# EDCPSUMK1-RP2040-USBC.net
KiCad netlist of a schematic drawn in EAGLE
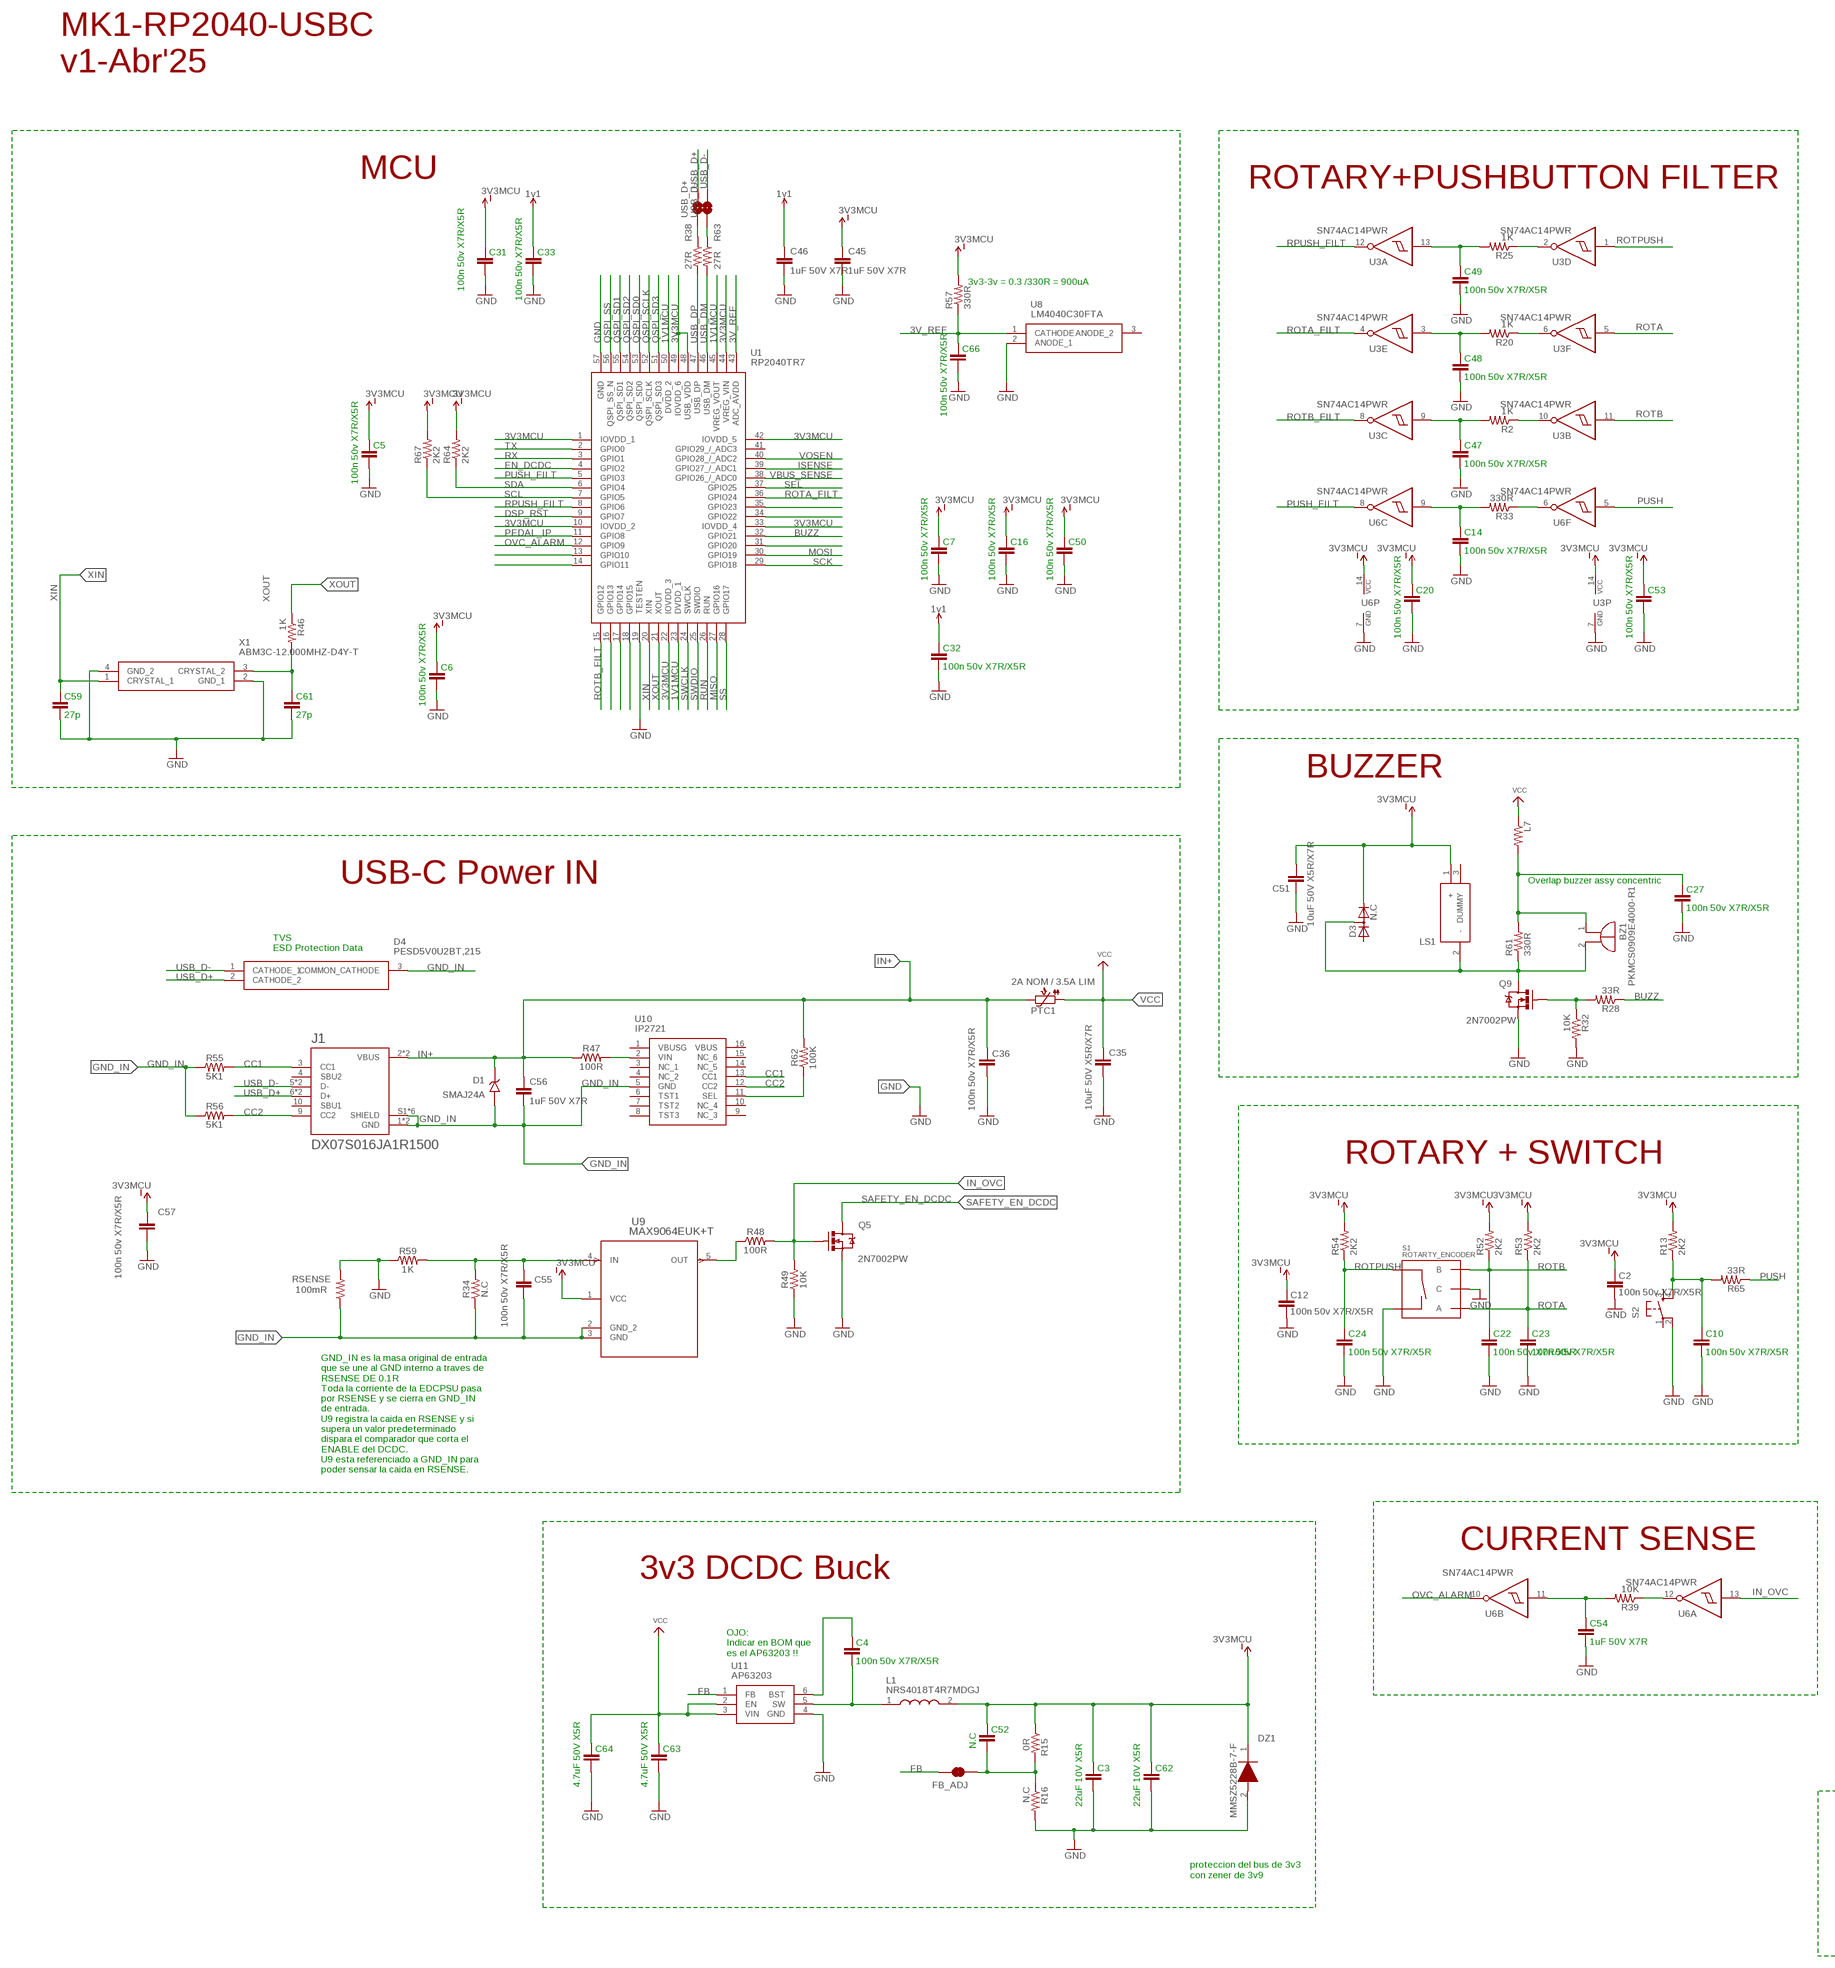
[diagram p0: schematic, sheet 1, part 1 of 2]
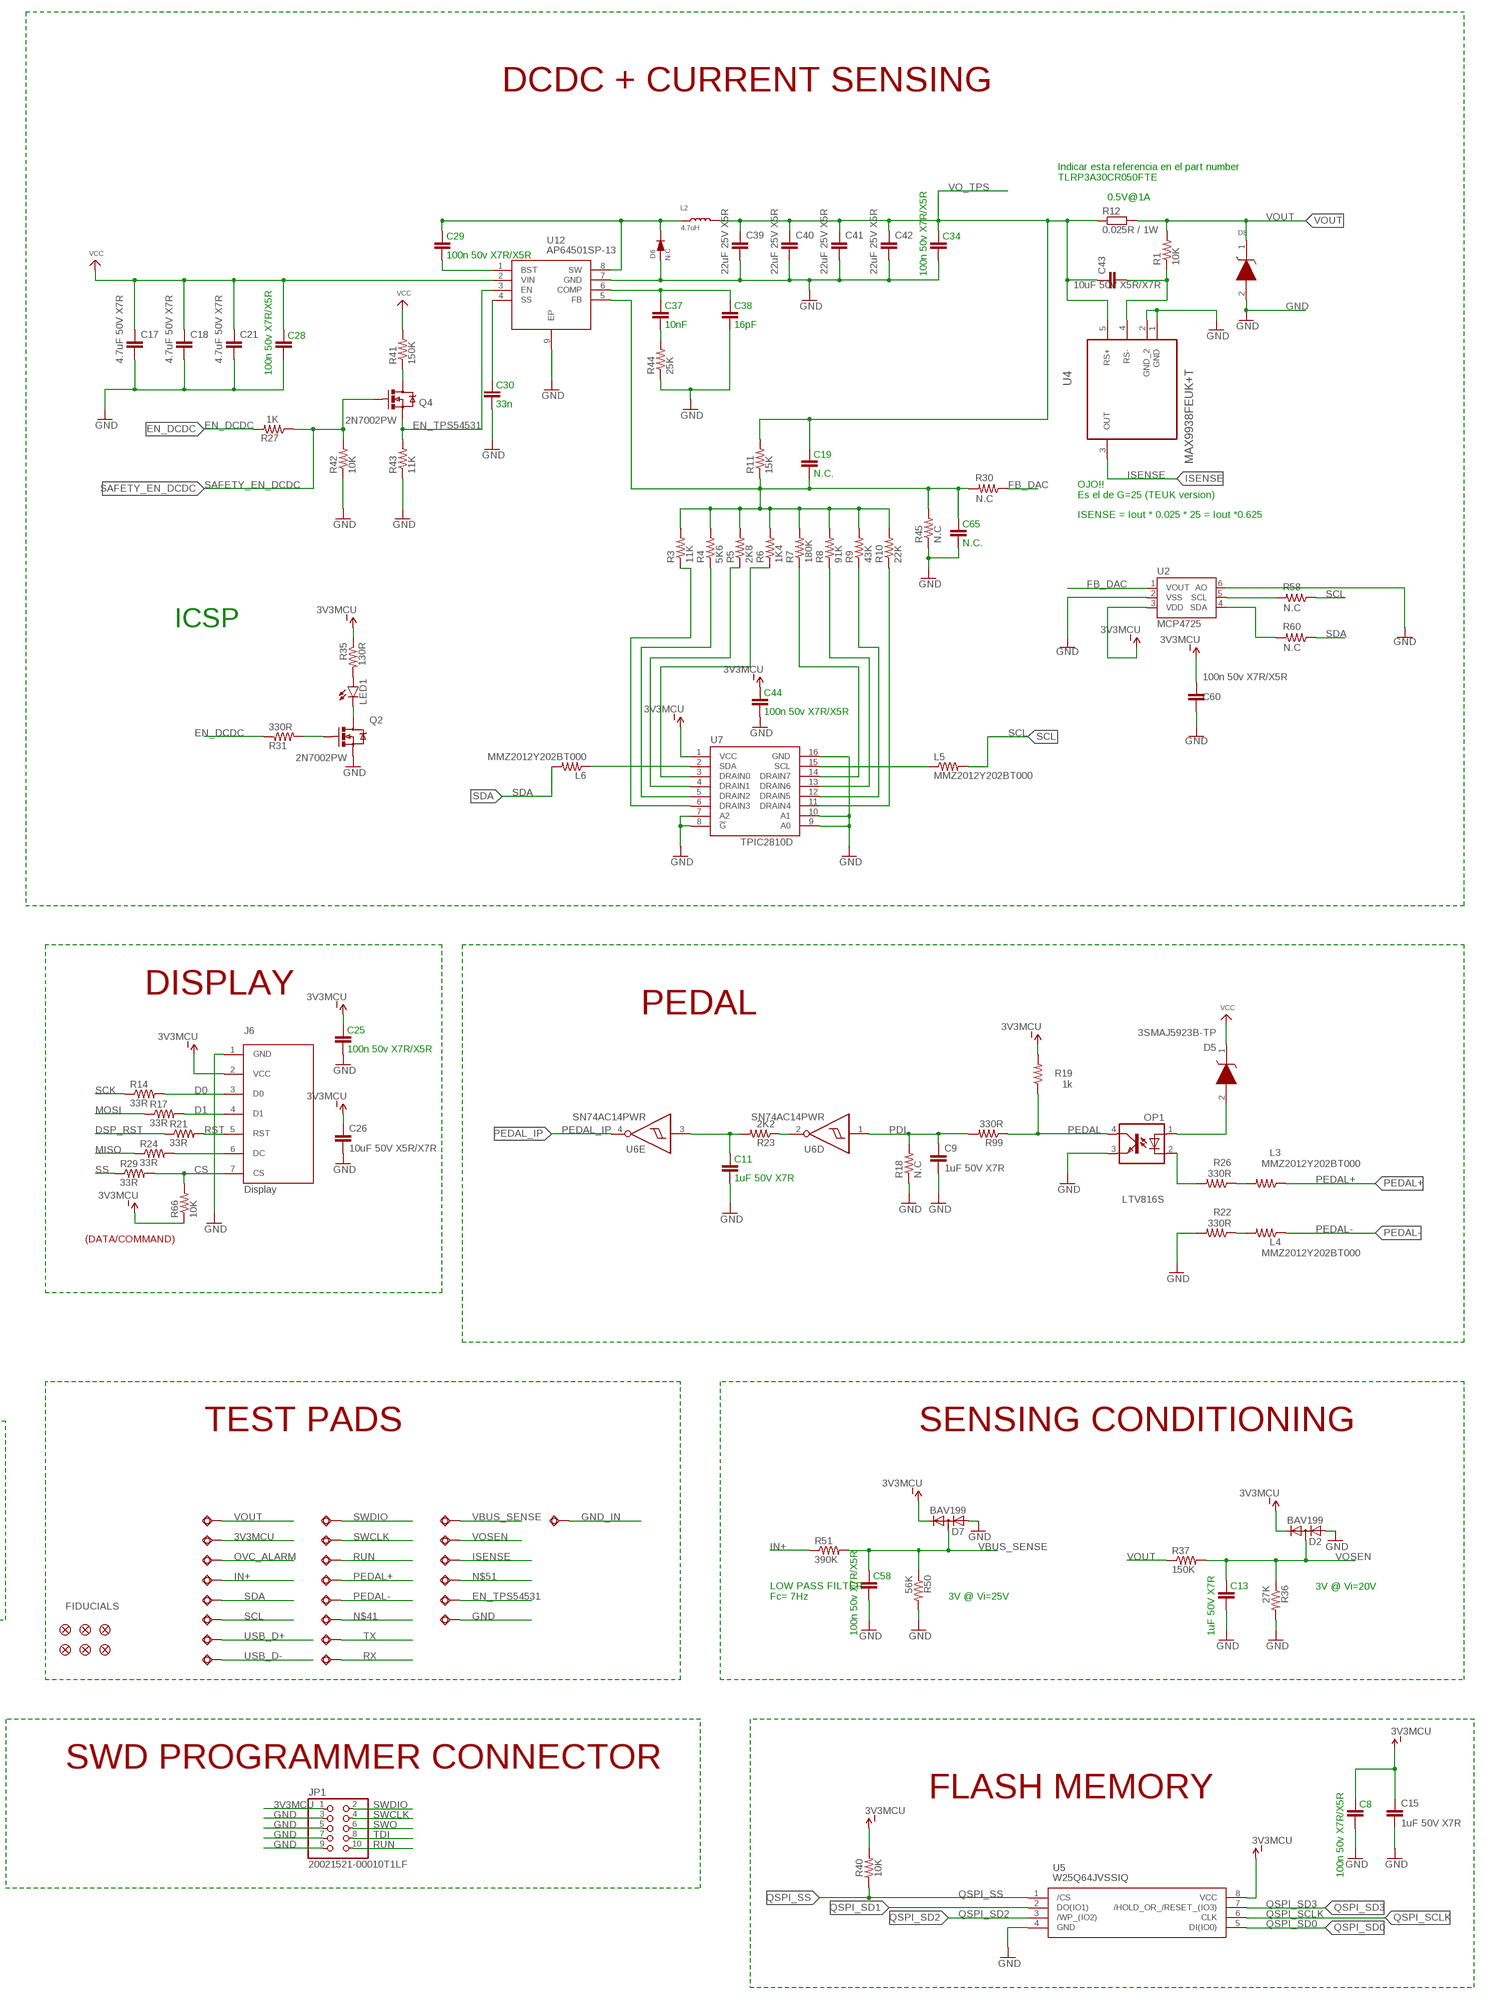
[diagram p1: schematic, sheet 1, part 2 of 2]

(export (version "E")
  (design (tool "Eeschema 10.0.6"))
  (components
    (comp (ref "3V3MCU")
      (value "TESTPAD_TPSQB1,27")
      (footprint "eagle-import:TESTPAD_B1,27")
      (libsource (lib "eagle-import") (part "TESTPAD_TPSQB1,27"))
    )
    (comp (ref "BZ1")
      (value "PKMCS0909E4000-R1")
      (footprint "eagle-import:PKMCS0909")
      (libsource (lib "eagle-import") (part "PKMCS0909E4000-R1"))
    )
    (comp (ref "C2")
      (value "100n 50v X7R/X5R")
      (footprint "eagle-import:0805")
      (libsource (lib "eagle-import") (part "CAP0805"))
    )
    (comp (ref "C3")
      (value "22uF 10V X5R")
      (footprint "eagle-import:0805")
      (libsource (lib "eagle-import") (part "CAP0805"))
    )
    (comp (ref "C4")
      (value "100n 50v X7R/X5R")
      (footprint "eagle-import:0805")
      (libsource (lib "eagle-import") (part "CAP0805"))
    )
    (comp (ref "C5")
      (value "100n 50v X7R/X5R")
      (footprint "eagle-import:0805")
      (libsource (lib "eagle-import") (part "CAP0805"))
    )
    (comp (ref "C6")
      (value "100n 50v X7R/X5R")
      (footprint "eagle-import:0805")
      (libsource (lib "eagle-import") (part "CAP0805"))
    )
    (comp (ref "C7")
      (value "100n 50v X7R/X5R")
      (footprint "eagle-import:0805")
      (libsource (lib "eagle-import") (part "CAP0805"))
    )
    (comp (ref "C8")
      (value "100n 50v X7R/X5R")
      (footprint "eagle-import:0805")
      (libsource (lib "eagle-import") (part "CAP0805"))
    )
    (comp (ref "C9")
      (value "1uF 50V X7R")
      (footprint "eagle-import:0805")
      (libsource (lib "eagle-import") (part "CAP0805"))
    )
    (comp (ref "C10")
      (value "100n 50v X7R/X5R")
      (footprint "eagle-import:0805")
      (libsource (lib "eagle-import") (part "CAP0805"))
    )
    (comp (ref "C11")
      (value "1uF 50V X7R")
      (footprint "eagle-import:0805")
      (libsource (lib "eagle-import") (part "CAP0805"))
    )
    (comp (ref "C12")
      (value "100n 50v X7R/X5R")
      (footprint "eagle-import:0805")
      (libsource (lib "eagle-import") (part "CAP0805"))
    )
    (comp (ref "C13")
      (value "1uF 50V X7R")
      (footprint "eagle-import:0805")
      (libsource (lib "eagle-import") (part "CAP0805"))
    )
    (comp (ref "C14")
      (value "100n 50v X7R/X5R")
      (footprint "eagle-import:0805")
      (libsource (lib "eagle-import") (part "CAP0805"))
    )
    (comp (ref "C15")
      (value "1uF 50V X7R")
      (footprint "eagle-import:0805")
      (libsource (lib "eagle-import") (part "CAP0805"))
    )
    (comp (ref "C16")
      (value "100n 50v X7R/X5R")
      (footprint "eagle-import:0805")
      (libsource (lib "eagle-import") (part "CAP0805"))
    )
    (comp (ref "C17")
      (value "4.7uF 50V X7R")
      (footprint "eagle-import:1210")
      (libsource (lib "eagle-import") (part "CAP1210"))
    )
    (comp (ref "C18")
      (value "4.7uF 50V X7R")
      (footprint "eagle-import:1210")
      (libsource (lib "eagle-import") (part "CAP1210"))
    )
    (comp (ref "C19")
      (value "N.C.")
      (footprint "eagle-import:0805")
      (libsource (lib "eagle-import") (part "CAP0805"))
    )
    (comp (ref "C20")
      (value "100n 50v X7R/X5R")
      (footprint "eagle-import:0805")
      (libsource (lib "eagle-import") (part "CAP0805"))
    )
    (comp (ref "C21")
      (value "4.7uF 50V X7R")
      (footprint "eagle-import:1210")
      (libsource (lib "eagle-import") (part "CAP1210"))
    )
    (comp (ref "C22")
      (value "100n 50v X7R/X5R")
      (footprint "eagle-import:0805")
      (libsource (lib "eagle-import") (part "CAP0805"))
    )
    (comp (ref "C23")
      (value "100n 50v X7R/X5R")
      (footprint "eagle-import:0805")
      (libsource (lib "eagle-import") (part "CAP0805"))
    )
    (comp (ref "C24")
      (value "100n 50v X7R/X5R")
      (footprint "eagle-import:0805")
      (libsource (lib "eagle-import") (part "CAP0805"))
    )
    (comp (ref "C25")
      (value "100n 50v X7R/X5R")
      (footprint "eagle-import:0805")
      (libsource (lib "eagle-import") (part "CAP0805"))
    )
    (comp (ref "C26")
      (value "10uF 50V X5R/X7R")
      (footprint "eagle-import:1206")
      (libsource (lib "eagle-import") (part "CAP1206"))
    )
    (comp (ref "C27")
      (value "100n 50v X7R/X5R")
      (footprint "eagle-import:0805")
      (libsource (lib "eagle-import") (part "CAP0805"))
    )
    (comp (ref "C28")
      (value "100n 50v X7R/X5R")
      (footprint "eagle-import:0805")
      (libsource (lib "eagle-import") (part "CAP0805"))
    )
    (comp (ref "C29")
      (value "100n 50v X7R/X5R")
      (footprint "eagle-import:0805")
      (libsource (lib "eagle-import") (part "CAP0805"))
    )
    (comp (ref "C30")
      (value "33n")
      (footprint "eagle-import:0805")
      (libsource (lib "eagle-import") (part "CAP0805"))
    )
    (comp (ref "C31")
      (value "100n 50v X7R/X5R")
      (footprint "eagle-import:0805")
      (libsource (lib "eagle-import") (part "CAP0805"))
    )
    (comp (ref "C32")
      (value "100n 50v X7R/X5R")
      (footprint "eagle-import:0805")
      (libsource (lib "eagle-import") (part "CAP0805"))
    )
    (comp (ref "C33")
      (value "100n 50v X7R/X5R")
      (footprint "eagle-import:0805")
      (libsource (lib "eagle-import") (part "CAP0805"))
    )
    (comp (ref "C34")
      (value "100n 50v X7R/X5R")
      (footprint "eagle-import:0805")
      (libsource (lib "eagle-import") (part "CAP0805"))
    )
    (comp (ref "C35")
      (value "10uF 50V X5R/X7R")
      (footprint "eagle-import:1206")
      (libsource (lib "eagle-import") (part "CAP1206"))
    )
    (comp (ref "C36")
      (value "100n 50v X7R/X5R")
      (footprint "eagle-import:0805")
      (libsource (lib "eagle-import") (part "CAP0805"))
    )
    (comp (ref "C37")
      (value "10nF")
      (footprint "eagle-import:0805")
      (libsource (lib "eagle-import") (part "CAP0805"))
    )
    (comp (ref "C38")
      (value "16pF")
      (footprint "eagle-import:0805")
      (libsource (lib "eagle-import") (part "CAP0805"))
    )
    (comp (ref "C39")
      (value "22uF 25V X5R")
      (footprint "eagle-import:1210")
      (libsource (lib "eagle-import") (part "CAP1210"))
    )
    (comp (ref "C40")
      (value "22uF 25V X5R")
      (footprint "eagle-import:1210")
      (libsource (lib "eagle-import") (part "CAP1210"))
    )
    (comp (ref "C41")
      (value "22uF 25V X5R")
      (footprint "eagle-import:1210")
      (libsource (lib "eagle-import") (part "CAP1210"))
    )
    (comp (ref "C42")
      (value "22uF 25V X5R")
      (footprint "eagle-import:1210")
      (libsource (lib "eagle-import") (part "CAP1210"))
    )
    (comp (ref "C43")
      (value "10uF 50V X5R/X7R")
      (footprint "eagle-import:1206")
      (libsource (lib "eagle-import") (part "CAP1206"))
    )
    (comp (ref "C44")
      (value "100n 50v X7R/X5R")
      (footprint "eagle-import:0805")
      (libsource (lib "eagle-import") (part "CAP0805"))
    )
    (comp (ref "C45")
      (value "1uF 50V X7R")
      (footprint "eagle-import:0805")
      (libsource (lib "eagle-import") (part "CAP0805"))
    )
    (comp (ref "C46")
      (value "1uF 50V X7R")
      (footprint "eagle-import:0805")
      (libsource (lib "eagle-import") (part "CAP0805"))
    )
    (comp (ref "C47")
      (value "100n 50v X7R/X5R")
      (footprint "eagle-import:0805")
      (libsource (lib "eagle-import") (part "CAP0805"))
    )
    (comp (ref "C48")
      (value "100n 50v X7R/X5R")
      (footprint "eagle-import:0805")
      (libsource (lib "eagle-import") (part "CAP0805"))
    )
    (comp (ref "C49")
      (value "100n 50v X7R/X5R")
      (footprint "eagle-import:0805")
      (libsource (lib "eagle-import") (part "CAP0805"))
    )
    (comp (ref "C50")
      (value "100n 50v X7R/X5R")
      (footprint "eagle-import:0805")
      (libsource (lib "eagle-import") (part "CAP0805"))
    )
    (comp (ref "C51")
      (value "10uF 50V X5R/X7R")
      (footprint "eagle-import:1206")
      (libsource (lib "eagle-import") (part "CAP1206"))
    )
    (comp (ref "C52")
      (value "N.C")
      (footprint "eagle-import:0805")
      (libsource (lib "eagle-import") (part "CAP0805"))
    )
    (comp (ref "C53")
      (value "100n 50v X7R/X5R")
      (footprint "eagle-import:0805")
      (libsource (lib "eagle-import") (part "CAP0805"))
    )
    (comp (ref "C54")
      (value "1uF 50V X7R")
      (footprint "eagle-import:0805")
      (libsource (lib "eagle-import") (part "CAP0805"))
    )
    (comp (ref "C55")
      (value "100n 50v X7R/X5R")
      (footprint "eagle-import:0805")
      (libsource (lib "eagle-import") (part "CAP0805"))
    )
    (comp (ref "C56")
      (value "1uF 50V X7R")
      (footprint "eagle-import:0805")
      (libsource (lib "eagle-import") (part "CAP0805"))
    )
    (comp (ref "C57")
      (value "100n 50v X7R/X5R")
      (footprint "eagle-import:0805")
      (libsource (lib "eagle-import") (part "CAP0805"))
    )
    (comp (ref "C58")
      (value "100n 50v X7R/X5R")
      (footprint "eagle-import:0805")
      (libsource (lib "eagle-import") (part "CAP0805"))
    )
    (comp (ref "C59")
      (value "27p")
      (footprint "eagle-import:0805")
      (libsource (lib "eagle-import") (part "CAP0805"))
    )
    (comp (ref "C60")
      (value "100n 50v X7R/X5R")
      (footprint "eagle-import:0805")
      (libsource (lib "eagle-import") (part "CAP0805"))
    )
    (comp (ref "C61")
      (value "27p")
      (footprint "eagle-import:0805")
      (libsource (lib "eagle-import") (part "CAP0805"))
    )
    (comp (ref "C62")
      (value "22uF 10V X5R")
      (footprint "eagle-import:0805")
      (libsource (lib "eagle-import") (part "CAP0805"))
    )
    (comp (ref "C63")
      (value "4.7uF 50V X5R")
      (footprint "eagle-import:0805")
      (libsource (lib "eagle-import") (part "CAP0805"))
    )
    (comp (ref "C64")
      (value "4.7uF 50V X5R")
      (footprint "eagle-import:0805")
      (libsource (lib "eagle-import") (part "CAP0805"))
    )
    (comp (ref "C65")
      (value "N.C.")
      (footprint "eagle-import:0805")
      (libsource (lib "eagle-import") (part "CAP0805"))
    )
    (comp (ref "C66")
      (value "100n 50v X7R/X5R")
      (footprint "eagle-import:0805")
      (libsource (lib "eagle-import") (part "CAP0805"))
    )
    (comp (ref "D1")
      (value "SMAJ24A")
      (footprint "eagle-import:DIOM4325X244N")
      (fields (field (name "MF") "Micro Commercial Components") (field (name "MP") "3SMAJ5934B"))
      (libsource (lib "eagle-import") (part "3SMAJ5934B"))
    )
    (comp (ref "D2")
      (value "BAV199")
      (footprint "eagle-import:SOT23")
      (libsource (lib "eagle-import") (part "BAV199"))
    )
    (comp (ref "D3")
      (value "N.C")
      (footprint "eagle-import:SOT23")
      (libsource (lib "eagle-import") (part "BAV199"))
    )
    (comp (ref "D4")
      (value "PESD5V0U2BT,215")
      (footprint "eagle-import:SOT95P230X110-3N")
      (fields (field (name "MOUSER_PART_NUMBER") "771-PESD5V0U2BTT/R"))
      (libsource (lib "eagle-import") (part "PESD5V0U2BT,215"))
    )
    (comp (ref "D5")
      (value "3SMAJ5923B-TP")
      (footprint "eagle-import:DIOM5226X244N")
      (fields (field (name "MOUSER_PART_NUMBER") "833-3SMAJ5923B-TP"))
      (libsource (lib "eagle-import") (part "3SMAJ5923B-TP"))
    )
    (comp (ref "D6")
      (value "N.C")
      (footprint "eagle-import:DO-214AB")
      (libsource (lib "eagle-import") (part "DSMC"))
    )
    (comp (ref "D7")
      (value "BAV199")
      (footprint "eagle-import:SOT23")
      (libsource (lib "eagle-import") (part "BAV199"))
    )
    (comp (ref "D8")
      (value "RB060M-60TR")
      (footprint "eagle-import:DIOM5226X244N")
      (fields
        (field (name "ARROW_PART_NUMBER") "3SMAJ5923B-TP")
        (field (name "MOUSER_PART_NUMBER") "833-3SMAJ5923B-TP")
      )
      (libsource (lib "eagle-import") (part "3SMAJ5923B-TP"))
    )
    (comp (ref "DZ1")
      (value "MMSZ5228B-7-F")
      (footprint "eagle-import:SODFL3518X115N")
      (libsource (lib "eagle-import") (part "MMSZ5228B-7-F"))
    )
    (comp (ref "EN_TPS54531")
      (value "TESTPAD_TPSQB1,27")
      (footprint "eagle-import:TESTPAD_B1,27")
      (libsource (lib "eagle-import") (part "TESTPAD_TPSQB1,27"))
    )
    (comp (ref "FB_ADJ")
      (value "JUMPER-SMT_2_NC_TRACE_NO-SILK")
      (footprint "eagle-import:SMT-JUMPER_2_NC_TRACE_NO-SILK")
      (libsource (lib "eagle-import") (part "JUMPER-SMT_2_NC_TRACE_NO-SILK"))
    )
    (comp (ref "FID1")
      (value "FIDUCIAL1X2")
      (footprint "eagle-import:FIDUCIAL-1X2")
      (libsource (lib "eagle-import") (part "FIDUCIAL1X2"))
    )
    (comp (ref "FID2")
      (value "FIDUCIAL1X2")
      (footprint "eagle-import:FIDUCIAL-1X2")
      (libsource (lib "eagle-import") (part "FIDUCIAL1X2"))
    )
    (comp (ref "FID3")
      (value "FIDUCIAL1X2")
      (footprint "eagle-import:FIDUCIAL-1X2")
      (libsource (lib "eagle-import") (part "FIDUCIAL1X2"))
    )
    (comp (ref "FID4")
      (value "FIDUCIAL1X2")
      (footprint "eagle-import:FIDUCIAL-1X2")
      (libsource (lib "eagle-import") (part "FIDUCIAL1X2"))
    )
    (comp (ref "FID5")
      (value "FIDUCIAL1X2")
      (footprint "eagle-import:FIDUCIAL-1X2")
      (libsource (lib "eagle-import") (part "FIDUCIAL1X2"))
    )
    (comp (ref "FID6")
      (value "FIDUCIAL1X2")
      (footprint "eagle-import:FIDUCIAL-1X2")
      (libsource (lib "eagle-import") (part "FIDUCIAL1X2"))
    )
    (comp (ref "GND")
      (value "TESTPAD_TPSQB1,27")
      (footprint "eagle-import:TESTPAD_B1,27")
      (libsource (lib "eagle-import") (part "TESTPAD_TPSQB1,27"))
    )
    (comp (ref "GND_IN")
      (value "TESTPAD_TPSQB1,27")
      (footprint "eagle-import:TESTPAD_B1,27")
      (libsource (lib "eagle-import") (part "TESTPAD_TPSQB1,27"))
    )
    (comp (ref "IN+")
      (value "TESTPAD_TPSQB1,27")
      (footprint "eagle-import:TESTPAD_B1,27")
      (libsource (lib "eagle-import") (part "TESTPAD_TPSQB1,27"))
    )
    (comp (ref "ISENSE")
      (value "TESTPAD_TPSQB1,27")
      (footprint "eagle-import:TESTPAD_B1,27")
      (libsource (lib "eagle-import") (part "TESTPAD_TPSQB1,27"))
    )
    (comp (ref "J1")
      (value "DX07S016JA1R1500")
      (footprint "eagle-import:JAE_DX07S016JA1R1500")
      (fields
        (field (name "DIGI-KEY_PART_NUMBER") "670-DX07S016JA1R1500CT-ND")
        (field (name "MF") "JAE Electronics")
      )
      (libsource (lib "eagle-import") (part "DX07S016JA1R1500"))
    )
    (comp (ref "J6")
      (value "Display")
      (footprint "eagle-import:OLED_LCD")
      (libsource (lib "eagle-import") (part "OLED_LCD"))
    )
    (comp (ref "JP1")
      (value "20021521-00010T1LF")
      (footprint "eagle-import:20021521-00010T1LF")
      (fields (field (name "DIGI-KEY_PART_NUMBER") "609-4054-ND") (field (name "MF") "AMPHENOL ICC / FCI"))
      (libsource (lib "eagle-import") (part "20021521-00010T1LF"))
    )
    (comp (ref "L1")
      (value "NRS4018T4R7MDGJ")
      (footprint "eagle-import:NRS4018T100MDGJ")
      (fields (field (name "MOUSER_PART_NUMBER") "963-NRS4018T4R7MDGJ"))
      (libsource (lib "eagle-import") (part "NRS4018T4R7MDGJ"))
    )
    (comp (ref "L2")
      (value "4.7uH")
      (footprint "eagle-import:WE-LHMI")
      (libsource (lib "eagle-import") (part "L74437368047"))
    )
    (comp (ref "L3")
      (value "MMZ2012Y202BT000")
      (footprint "eagle-import:0805")
      (libsource (lib "eagle-import") (part "RESISTOR0805-RES"))
    )
    (comp (ref "L4")
      (value "MMZ2012Y202BT000")
      (footprint "eagle-import:0805")
      (libsource (lib "eagle-import") (part "RESISTOR0805-RES"))
    )
    (comp (ref "L5")
      (value "MMZ2012Y202BT000")
      (footprint "eagle-import:0805")
      (libsource (lib "eagle-import") (part "RESISTOR0805-RES"))
    )
    (comp (ref "L6")
      (value "MMZ2012Y202BT000")
      (footprint "eagle-import:0805")
      (libsource (lib "eagle-import") (part "RESISTOR0805-RES"))
    )
    (comp (ref "L7")
      (value "MMZ2012Y202BT000")
      (footprint "eagle-import:0805")
      (libsource (lib "eagle-import") (part "RESISTOR0805-RES"))
    )
    (comp (ref "LED1")
      (value "LED3MM")
      (footprint "eagle-import:LED3MM")
      (libsource (lib "eagle-import") (part "LED3MM"))
    )
    (comp (ref "LS1")
      (value "SMT-0540-S-R")
      (footprint "eagle-import:SMT0540SR")
      (fields (field (name "MOUSER_PART_NUMBER") "665-SMT0540SR"))
      (libsource (lib "eagle-import") (part "SMT-0540-S-R"))
    )
    (comp (ref "N$41")
      (value "TESTPAD_TPSQB1,27")
      (footprint "eagle-import:TESTPAD_B1,27")
      (libsource (lib "eagle-import") (part "TESTPAD_TPSQB1,27"))
    )
    (comp (ref "N$51")
      (value "TESTPAD_TPSQB1,27")
      (footprint "eagle-import:TESTPAD_B1,27")
      (libsource (lib "eagle-import") (part "TESTPAD_TPSQB1,27"))
    )
    (comp (ref "OP1")
      (value "LTV816S")
      (footprint "eagle-import:SMD4")
      (libsource (lib "eagle-import") (part "LTV816S"))
    )
    (comp (ref "OVC_ALARM")
      (value "TESTPAD_TPSQB1,27")
      (footprint "eagle-import:TESTPAD_B1,27")
      (libsource (lib "eagle-import") (part "TESTPAD_TPSQB1,27"))
    )
    (comp (ref "PEDAL+")
      (value "TESTPAD_TPSQB1,27")
      (footprint "eagle-import:TESTPAD_B1,27")
      (libsource (lib "eagle-import") (part "TESTPAD_TPSQB1,27"))
    )
    (comp (ref "PEDAL-")
      (value "TESTPAD_TPSQB1,27")
      (footprint "eagle-import:TESTPAD_B1,27")
      (libsource (lib "eagle-import") (part "TESTPAD_TPSQB1,27"))
    )
    (comp (ref "PTC1")
      (value "2A NOM / 3.5A LIM")
      (footprint "eagle-import:1812L")
      (libsource (lib "eagle-import") (part "PTC-"))
    )
    (comp (ref "Q2")
      (value "2N7002PW")
      (footprint "eagle-import:SOT323")
      (libsource (lib "eagle-import") (part "MOSFET-NCHANNEL2N7002PW"))
    )
    (comp (ref "Q4")
      (value "2N7002PW")
      (footprint "eagle-import:SOT323")
      (libsource (lib "eagle-import") (part "MOSFET-NCHANNEL2N7002PW"))
    )
    (comp (ref "Q5")
      (value "2N7002PW")
      (footprint "eagle-import:SOT323")
      (libsource (lib "eagle-import") (part "MOSFET-NCHANNEL2N7002PW"))
    )
    (comp (ref "Q9")
      (value "2N7002PW")
      (footprint "eagle-import:SOT323")
      (libsource (lib "eagle-import") (part "MOSFET-NCHANNEL2N7002PW"))
    )
    (comp (ref "R1")
      (value "10K")
      (footprint "eagle-import:0805")
      (libsource (lib "eagle-import") (part "RESISTOR0805"))
    )
    (comp (ref "R2")
      (value "1K")
      (footprint "eagle-import:0805")
      (libsource (lib "eagle-import") (part "RESISTOR0805"))
    )
    (comp (ref "R3")
      (value "11K")
      (footprint "eagle-import:0805")
      (libsource (lib "eagle-import") (part "RESISTOR0805"))
    )
    (comp (ref "R4")
      (value "5K6")
      (footprint "eagle-import:0805")
      (libsource (lib "eagle-import") (part "RESISTOR0805"))
    )
    (comp (ref "R5")
      (value "2K8")
      (footprint "eagle-import:0805")
      (libsource (lib "eagle-import") (part "RESISTOR0805"))
    )
    (comp (ref "R6")
      (value "1K4")
      (footprint "eagle-import:0805")
      (libsource (lib "eagle-import") (part "RESISTOR0805"))
    )
    (comp (ref "R7")
      (value "180K")
      (footprint "eagle-import:0805")
      (libsource (lib "eagle-import") (part "RESISTOR0805"))
    )
    (comp (ref "R8")
      (value "91K")
      (footprint "eagle-import:0805")
      (libsource (lib "eagle-import") (part "RESISTOR0805"))
    )
    (comp (ref "R9")
      (value "43K")
      (footprint "eagle-import:0805")
      (libsource (lib "eagle-import") (part "RESISTOR0805"))
    )
    (comp (ref "R10")
      (value "22K")
      (footprint "eagle-import:0805")
      (libsource (lib "eagle-import") (part "RESISTOR0805"))
    )
    (comp (ref "R11")
      (value "15K")
      (footprint "eagle-import:0805")
      (libsource (lib "eagle-import") (part "RESISTOR0805"))
    )
    (comp (ref "R12")
      (value "0.025R / 1W")
      (footprint "eagle-import:R2512")
      (libsource (lib "eagle-import") (part "RR2512"))
    )
    (comp (ref "R13")
      (value "2K2")
      (footprint "eagle-import:0805")
      (libsource (lib "eagle-import") (part "RESISTOR0805"))
    )
    (comp (ref "R14")
      (value "33R")
      (footprint "eagle-import:0805")
      (libsource (lib "eagle-import") (part "RESISTOR0805"))
    )
    (comp (ref "R15")
      (value "0R")
      (footprint "eagle-import:0805")
      (libsource (lib "eagle-import") (part "RESISTOR0805"))
    )
    (comp (ref "R16")
      (value "N.C")
      (footprint "eagle-import:0805")
      (libsource (lib "eagle-import") (part "RESISTOR0805"))
    )
    (comp (ref "R17")
      (value "33R")
      (footprint "eagle-import:0805")
      (libsource (lib "eagle-import") (part "RESISTOR0805"))
    )
    (comp (ref "R18")
      (value "N.C")
      (footprint "eagle-import:0805")
      (libsource (lib "eagle-import") (part "RESISTOR0805"))
    )
    (comp (ref "R19")
      (value "1k")
      (footprint "eagle-import:0805")
      (libsource (lib "eagle-import") (part "RESISTOR0805"))
    )
    (comp (ref "R20")
      (value "1K")
      (footprint "eagle-import:0805")
      (libsource (lib "eagle-import") (part "RESISTOR0805"))
    )
    (comp (ref "R21")
      (value "33R")
      (footprint "eagle-import:0805")
      (libsource (lib "eagle-import") (part "RESISTOR0805"))
    )
    (comp (ref "R22")
      (value "330R")
      (footprint "eagle-import:0805")
      (libsource (lib "eagle-import") (part "RESISTOR0805"))
    )
    (comp (ref "R23")
      (value "2K2")
      (footprint "eagle-import:0805")
      (libsource (lib "eagle-import") (part "RESISTOR0805"))
    )
    (comp (ref "R24")
      (value "33R")
      (footprint "eagle-import:0805")
      (libsource (lib "eagle-import") (part "RESISTOR0805"))
    )
    (comp (ref "R25")
      (value "1K")
      (footprint "eagle-import:0805")
      (libsource (lib "eagle-import") (part "RESISTOR0805"))
    )
    (comp (ref "R26")
      (value "330R")
      (footprint "eagle-import:0805")
      (libsource (lib "eagle-import") (part "RESISTOR0805"))
    )
    (comp (ref "R27")
      (value "1K")
      (footprint "eagle-import:0805")
      (libsource (lib "eagle-import") (part "RESISTOR0805"))
    )
    (comp (ref "R28")
      (value "33R")
      (footprint "eagle-import:0805")
      (libsource (lib "eagle-import") (part "RESISTOR0805"))
    )
    (comp (ref "R29")
      (value "33R")
      (footprint "eagle-import:0805")
      (libsource (lib "eagle-import") (part "RESISTOR0805"))
    )
    (comp (ref "R30")
      (value "N.C")
      (footprint "eagle-import:0805")
      (libsource (lib "eagle-import") (part "RESISTOR0805"))
    )
    (comp (ref "R31")
      (value "330R")
      (footprint "eagle-import:0805")
      (libsource (lib "eagle-import") (part "RESISTOR0805"))
    )
    (comp (ref "R32")
      (value "10K")
      (footprint "eagle-import:0805")
      (libsource (lib "eagle-import") (part "RESISTOR0805"))
    )
    (comp (ref "R33")
      (value "330R")
      (footprint "eagle-import:0805")
      (libsource (lib "eagle-import") (part "RESISTOR0805"))
    )
    (comp (ref "R34")
      (value "N.C")
      (footprint "eagle-import:0805")
      (libsource (lib "eagle-import") (part "RESISTOR0805"))
    )
    (comp (ref "R35")
      (value "130R")
      (footprint "eagle-import:0805")
      (libsource (lib "eagle-import") (part "RESISTOR0805"))
    )
    (comp (ref "R36")
      (value "27K")
      (footprint "eagle-import:0805")
      (libsource (lib "eagle-import") (part "RESISTOR0805"))
    )
    (comp (ref "R37")
      (value "150K")
      (footprint "eagle-import:0805")
      (libsource (lib "eagle-import") (part "RESISTOR0805"))
    )
    (comp (ref "R38")
      (value "27R")
      (footprint "eagle-import:0805")
      (libsource (lib "eagle-import") (part "RESISTOR0805"))
    )
    (comp (ref "R39")
      (value "10K")
      (footprint "eagle-import:0805")
      (libsource (lib "eagle-import") (part "RESISTOR0805"))
    )
    (comp (ref "R40")
      (value "10K")
      (footprint "eagle-import:0805")
      (libsource (lib "eagle-import") (part "RESISTOR0805"))
    )
    (comp (ref "R41")
      (value "150K")
      (footprint "eagle-import:0805")
      (libsource (lib "eagle-import") (part "RESISTOR0805"))
    )
    (comp (ref "R42")
      (value "10K")
      (footprint "eagle-import:0805")
      (libsource (lib "eagle-import") (part "RESISTOR0805"))
    )
    (comp (ref "R43")
      (value "11K")
      (footprint "eagle-import:0805")
      (libsource (lib "eagle-import") (part "RESISTOR0805"))
    )
    (comp (ref "R44")
      (value "25K")
      (footprint "eagle-import:0805")
      (libsource (lib "eagle-import") (part "RESISTOR0805"))
    )
    (comp (ref "R45")
      (value "N.C")
      (footprint "eagle-import:0805")
      (libsource (lib "eagle-import") (part "RESISTOR0805"))
    )
    (comp (ref "R46")
      (value "1K")
      (footprint "eagle-import:0805")
      (libsource (lib "eagle-import") (part "RESISTOR0805"))
    )
    (comp (ref "R47")
      (value "100R")
      (footprint "eagle-import:0805")
      (libsource (lib "eagle-import") (part "RESISTOR0805"))
    )
    (comp (ref "R48")
      (value "100R")
      (footprint "eagle-import:0805")
      (libsource (lib "eagle-import") (part "RESISTOR0805"))
    )
    (comp (ref "R49")
      (value "10K")
      (footprint "eagle-import:0805")
      (libsource (lib "eagle-import") (part "RESISTOR0805"))
    )
    (comp (ref "R50")
      (value "56K")
      (footprint "eagle-import:0805")
      (libsource (lib "eagle-import") (part "RESISTOR0805"))
    )
    (comp (ref "R51")
      (value "390K")
      (footprint "eagle-import:0805")
      (libsource (lib "eagle-import") (part "RESISTOR0805"))
    )
    (comp (ref "R52")
      (value "2K2")
      (footprint "eagle-import:0805")
      (libsource (lib "eagle-import") (part "RESISTOR0805"))
    )
    (comp (ref "R53")
      (value "2K2")
      (footprint "eagle-import:0805")
      (libsource (lib "eagle-import") (part "RESISTOR0805"))
    )
    (comp (ref "R54")
      (value "2K2")
      (footprint "eagle-import:0805")
      (libsource (lib "eagle-import") (part "RESISTOR0805"))
    )
    (comp (ref "R55")
      (value "5K1")
      (footprint "eagle-import:0805")
      (libsource (lib "eagle-import") (part "RESISTOR0805"))
    )
    (comp (ref "R56")
      (value "5K1")
      (footprint "eagle-import:0805")
      (libsource (lib "eagle-import") (part "RESISTOR0805"))
    )
    (comp (ref "R57")
      (value "330R")
      (footprint "eagle-import:0805")
      (libsource (lib "eagle-import") (part "RESISTOR0805"))
    )
    (comp (ref "R58")
      (value "N.C")
      (footprint "eagle-import:0805")
      (libsource (lib "eagle-import") (part "RESISTOR0805"))
    )
    (comp (ref "R59")
      (value "1K")
      (footprint "eagle-import:0805")
      (libsource (lib "eagle-import") (part "RESISTOR0805"))
    )
    (comp (ref "R60")
      (value "N.C")
      (footprint "eagle-import:0805")
      (libsource (lib "eagle-import") (part "RESISTOR0805"))
    )
    (comp (ref "R61")
      (value "330R")
      (footprint "eagle-import:0805")
      (libsource (lib "eagle-import") (part "RESISTOR0805"))
    )
    (comp (ref "R62")
      (value "100K")
      (footprint "eagle-import:0805")
      (libsource (lib "eagle-import") (part "RESISTOR0805"))
    )
    (comp (ref "R63")
      (value "27R")
      (footprint "eagle-import:0805")
      (libsource (lib "eagle-import") (part "RESISTOR0805"))
    )
    (comp (ref "R64")
      (value "2K2")
      (footprint "eagle-import:0805")
      (libsource (lib "eagle-import") (part "RESISTOR0805"))
    )
    (comp (ref "R65")
      (value "33R")
      (footprint "eagle-import:0805")
      (libsource (lib "eagle-import") (part "RESISTOR0805"))
    )
    (comp (ref "R66")
      (value "10K")
      (footprint "eagle-import:0805")
      (libsource (lib "eagle-import") (part "RESISTOR0805"))
    )
    (comp (ref "R67")
      (value "2K2")
      (footprint "eagle-import:0805")
      (libsource (lib "eagle-import") (part "RESISTOR0805"))
    )
    (comp (ref "R99")
      (value "330R")
      (footprint "eagle-import:0805")
      (libsource (lib "eagle-import") (part "RESISTOR0805"))
    )
    (comp (ref "RSENSE")
      (value "100mR")
      (footprint "eagle-import:1206")
      (libsource (lib "eagle-import") (part "SparkFun-Resistors_532_RESISTOR1206"))
    )
    (comp (ref "RUN")
      (value "TESTPAD_TPSQB1,27")
      (footprint "eagle-import:TESTPAD_B1,27")
      (libsource (lib "eagle-import") (part "TESTPAD_TPSQB1,27"))
    )
    (comp (ref "RX")
      (value "TESTPAD_TPSQB1,27")
      (footprint "eagle-import:TESTPAD_B1,27")
      (libsource (lib "eagle-import") (part "TESTPAD_TPSQB1,27"))
    )
    (comp (ref "S1")
      (value "ROTARTY_ENCODER")
      (footprint "eagle-import:ROTARY_ENC_PLAIN")
      (libsource (lib "eagle-import") (part "ROTARTY_ENCODER"))
    )
    (comp (ref "S2")
      (value "TAC_SWITCH_KSC931G-SMD")
      (footprint "eagle-import:TAC_SW_SMD_KSC931G")
      (libsource (lib "eagle-import") (part "TAC_SWITCH_KSC931G-SMD"))
    )
    (comp (ref "SCL")
      (value "TESTPAD_TPSQB1,27")
      (footprint "eagle-import:TESTPAD_B1,27")
      (libsource (lib "eagle-import") (part "TESTPAD_TPSQB1,27"))
    )
    (comp (ref "SDA")
      (value "TESTPAD_TPSQB1,27")
      (footprint "eagle-import:TESTPAD_B1,27")
      (libsource (lib "eagle-import") (part "TESTPAD_TPSQB1,27"))
    )
    (comp (ref "SWCLK")
      (value "TESTPAD_TPSQB1,27")
      (footprint "eagle-import:TESTPAD_B1,27")
      (libsource (lib "eagle-import") (part "TESTPAD_TPSQB1,27"))
    )
    (comp (ref "SWDIO")
      (value "TESTPAD_TPSQB1,27")
      (footprint "eagle-import:TESTPAD_B1,27")
      (libsource (lib "eagle-import") (part "TESTPAD_TPSQB1,27"))
    )
    (comp (ref "TX")
      (value "TESTPAD_TPSQB1,27")
      (footprint "eagle-import:TESTPAD_B1,27")
      (libsource (lib "eagle-import") (part "TESTPAD_TPSQB1,27"))
    )
    (comp (ref "U1")
      (value "RP2040TR7")
      (footprint "eagle-import:RP2040TR7")
      (libsource (lib "eagle-import") (part "RP2040TR7"))
    )
    (comp (ref "U2")
      (value "MCP4725")
      (footprint "eagle-import:SOT23-6")
      (libsource (lib "eagle-import") (part "MCP4725SOT-23"))
    )
    (comp (ref "U3")
      (value "SN74AC14PWR")
      (footprint "eagle-import:TSSOP14")
      (libsource (lib "eagle-import") (part "7414"))
    )
    (comp (ref "U4")
      (value "MAX9938FEUK+T")
      (footprint "eagle-import:SOT95P280X145-5N")
      (libsource (lib "eagle-import") (part "MAX9938FEUK+T"))
    )
    (comp (ref "U5")
      (value "W25Q64JVSSIQ")
      (footprint "eagle-import:SOIC127P790X216-8N")
      (fields (field (name "MOUSER_PART_NUMBER") "454-W25Q64JVSSIQ"))
      (libsource (lib "eagle-import") (part "W25Q64JVSSIQ"))
    )
    (comp (ref "U6")
      (value "SN74AC14PWR")
      (footprint "eagle-import:TSSOP14")
      (libsource (lib "eagle-import") (part "7414"))
    )
    (comp (ref "U7")
      (value "TPIC2810D")
      (footprint "eagle-import:SO16")
      (libsource (lib "eagle-import") (part "TPIC2810D"))
    )
    (comp (ref "U8")
      (value "LM4040C30FTA")
      (footprint "eagle-import:SOT96P240X120-3N")
      (fields (field (name "MOUSER_PART_NUMBER") "621-LM4040C30FTA"))
      (libsource (lib "eagle-import") (part "LM4040C30FTA"))
    )
    (comp (ref "U9")
      (value "MAX9064EUK+T")
      (footprint "eagle-import:21-0057F_MXM")
      (fields (field (name "COPYRIGHT") "Copyright (C) 2022 Ultra Librarian. All rights reserved."))
      (libsource (lib "eagle-import") (part "MAX9064EUK+T"))
    )
    (comp (ref "U10")
      (value "IP2721")
      (footprint "eagle-import:SOP65P640X120-16N")
      (libsource (lib "eagle-import") (part "IP2721"))
    )
    (comp (ref "U11")
      (value "AP63203")
      (footprint "eagle-import:SOT95P280X100-6N")
      (fields
        (field (name "ARROW_PART_NUMBER") "AP63201WU-7")
        (field (name "MOUSER_PART_NUMBER") "621-AP63201WU-7")
      )
      (libsource (lib "eagle-import") (part "AP63201WU-7"))
    )
    (comp (ref "U12")
      (value "AP64501SP-13")
      (footprint "eagle-import:SOIC127P600X163-9N")
      (fields (field (name "MOUSER_PART_NUMBER") "621-AP64501SP-13"))
      (libsource (lib "eagle-import") (part "AP64501SP-13"))
    )
    (comp (ref "USB-D+")
      (value "TESTPAD_TPSQB1,27")
      (footprint "eagle-import:TESTPAD_B1,27")
      (libsource (lib "eagle-import") (part "TESTPAD_TPSQB1,27"))
    )
    (comp (ref "USB-D-")
      (value "TESTPAD_TPSQB1,27")
      (footprint "eagle-import:TESTPAD_B1,27")
      (libsource (lib "eagle-import") (part "TESTPAD_TPSQB1,27"))
    )
    (comp (ref "USB_D+")
      (value "JUMPER-SMT_2_NO_NO-SILK")
      (footprint "eagle-import:SMT-JUMPER_2_NO_NO-SILK")
      (libsource (lib "eagle-import") (part "JUMPER-SMT_2_NO_NO-SILK"))
    )
    (comp (ref "USB_D-")
      (value "JUMPER-SMT_2_NO_NO-SILK")
      (footprint "eagle-import:SMT-JUMPER_2_NO_NO-SILK")
      (libsource (lib "eagle-import") (part "JUMPER-SMT_2_NO_NO-SILK"))
    )
    (comp (ref "VBUS_SENSE")
      (value "TESTPAD_TPSQB1,27")
      (footprint "eagle-import:TESTPAD_B1,27")
      (libsource (lib "eagle-import") (part "TESTPAD_TPSQB1,27"))
    )
    (comp (ref "VOSEN")
      (value "TESTPAD_TPSQB1,27")
      (footprint "eagle-import:TESTPAD_B1,27")
      (libsource (lib "eagle-import") (part "TESTPAD_TPSQB1,27"))
    )
    (comp (ref "VOUT")
      (value "TESTPAD_TPSQB1,27")
      (footprint "eagle-import:TESTPAD_B1,27")
      (libsource (lib "eagle-import") (part "TESTPAD_TPSQB1,27"))
    )
    (comp (ref "X1")
      (value "ABM3C-12.000MHZ-D4Y-T")
      (footprint "eagle-import:ABM3C16000MHZD4YT")
      (fields (field (name "MOUSER_PART_NUMBER") "815-ABM3C-12-D4YT"))
      (libsource (lib "eagle-import") (part "ABM3C-12.000MHZ-D4Y-T"))
    )
  )
  (nets
    (net (code "1") (name "/3V_REF") (class "Default")
      (node (ref "C66") (pin "2") (pinfunction "2_2") (pintype "passive"))
      (node (ref "R57") (pin "1") (pinfunction "1_1") (pintype "passive"))
      (node (ref "U1") (pin "43") (pinfunction "ADC_AVDD_43") (pintype "bidirectional"))
      (node (ref "U8") (pin "1") (pinfunction "CATHODE_1") (pintype "bidirectional"))
    )
    (net (code "2") (name "/BUZZ") (class "Default")
      (node (ref "R28") (pin "1") (pinfunction "1_1") (pintype "passive"))
      (node (ref "U1") (pin "32") (pinfunction "GPIO21_32") (pintype "bidirectional"))
    )
    (net (code "3") (name "/CC1") (class "Default")
      (node (ref "J1") (pin "3") (pinfunction "CC1_3") (pintype "passive"))
      (node (ref "R55") (pin "2") (pinfunction "2_2") (pintype "passive"))
      (node (ref "U10") (pin "13") (pinfunction "CC1_13") (pintype "bidirectional"))
    )
    (net (code "4") (name "/CC2") (class "Default")
      (node (ref "J1") (pin "9") (pinfunction "CC2_9") (pintype "passive"))
      (node (ref "R56") (pin "2") (pinfunction "2_2") (pintype "passive"))
      (node (ref "U10") (pin "12") (pinfunction "CC2_12") (pintype "bidirectional"))
    )
    (net (code "5") (name "/CS") (class "Default")
      (node (ref "J6") (pin "7") (pinfunction "CS_7") (pintype "bidirectional"))
      (node (ref "R29") (pin "2") (pinfunction "2_2") (pintype "passive"))
      (node (ref "R66") (pin "2") (pinfunction "2_2") (pintype "passive"))
    )
    (net (code "6") (name "/D0") (class "Default")
      (node (ref "J6") (pin "3") (pinfunction "D0_3") (pintype "bidirectional"))
      (node (ref "R14") (pin "2") (pinfunction "2_2") (pintype "passive"))
    )
    (net (code "7") (name "/D1") (class "Default")
      (node (ref "J6") (pin "4") (pinfunction "D1_4") (pintype "bidirectional"))
      (node (ref "R17") (pin "2") (pinfunction "2_2") (pintype "passive"))
    )
    (net (code "8") (name "/DSP_RST") (class "Default")
      (node (ref "R21") (pin "1") (pinfunction "1_1") (pintype "passive"))
      (node (ref "U1") (pin "9") (pinfunction "GPIO7_9") (pintype "bidirectional"))
    )
    (net (code "9") (name "/EN_TPS54531") (class "Default")
      (node (ref "EN_TPS54531") (pin "TP") (pinfunction "TP_TP") (pintype "input"))
      (node (ref "Q4") (pin "2") (pinfunction "S_2") (pintype "passive"))
      (node (ref "R43") (pin "2") (pinfunction "2_2") (pintype "passive"))
      (node (ref "U12") (pin "3") (pinfunction "EN_3") (pintype "bidirectional"))
    )
    (net (code "10") (name "/FB") (class "Default")
      (node (ref "FB_ADJ") (pin "2") (pinfunction "2_2") (pintype "passive"))
      (node (ref "U11") (pin "1") (pinfunction "FB_1") (pintype "bidirectional"))
    )
    (net (code "11") (name "/FB_DAC") (class "Default")
      (node (ref "R30") (pin "1") (pinfunction "1_1") (pintype "passive"))
      (node (ref "U2") (pin "1") (pinfunction "VOUT_1") (pintype "bidirectional"))
    )
    (net (code "12") (name "/MISO") (class "Default")
      (node (ref "R24") (pin "1") (pinfunction "1_1") (pintype "passive"))
      (node (ref "U1") (pin "27") (pinfunction "GPIO16_27") (pintype "bidirectional"))
    )
    (net (code "13") (name "/MOSI") (class "Default")
      (node (ref "R17") (pin "1") (pinfunction "1_1") (pintype "passive"))
      (node (ref "U1") (pin "30") (pinfunction "GPIO19_30") (pintype "bidirectional"))
    )
    (net (code "14") (name "/N$41") (class "Default")
      (node (ref "N$41") (pin "TP") (pinfunction "TP_TP") (pintype "input"))
      (node (ref "OP1") (pin "2") (pinfunction "C_2") (pintype "passive"))
      (node (ref "R26") (pin "2") (pinfunction "2_2") (pintype "passive"))
    )
    (net (code "15") (name "/N$51") (class "Default")
      (node (ref "C29") (pin "2") (pinfunction "2_2") (pintype "passive"))
      (node (ref "D6") (pin "2") (pinfunction "K_2") (pintype "bidirectional"))
      (node (ref "L2") (pin "1") (pinfunction "1_1") (pintype "passive"))
      (node (ref "N$51") (pin "TP") (pinfunction "TP_TP") (pintype "input"))
      (node (ref "U12") (pin "8") (pinfunction "SW_8") (pintype "bidirectional"))
    )
    (net (code "16") (name "/OVC_ALARM") (class "Default")
      (node (ref "OVC_ALARM") (pin "TP") (pinfunction "TP_TP") (pintype "input"))
      (node (ref "U1") (pin "12") (pinfunction "GPIO9_12") (pintype "bidirectional"))
      (node (ref "U6") (pin "10") (pinfunction "O_10") (pintype "output"))
    )
    (net (code "17") (name "/PDL") (class "Default")
      (node (ref "C9") (pin "1") (pinfunction "1_1") (pintype "passive"))
      (node (ref "R18") (pin "2") (pinfunction "2_2") (pintype "passive"))
      (node (ref "R99") (pin "2") (pinfunction "2_2") (pintype "passive"))
      (node (ref "U6") (pin "1") (pinfunction "I_1") (pintype "input"))
    )
    (net (code "18") (name "/PEDAL") (class "Default")
      (node (ref "OP1") (pin "4") (pinfunction "COL_4") (pintype "passive"))
      (node (ref "R19") (pin "1") (pinfunction "1_1") (pintype "passive"))
      (node (ref "R99") (pin "1") (pinfunction "1_1") (pintype "passive"))
    )
    (net (code "19") (name "/PUSH") (class "Default")
      (node (ref "R65") (pin "1") (pinfunction "1_1") (pintype "passive"))
      (node (ref "U6") (pin "5") (pinfunction "I_5") (pintype "input"))
    )
    (net (code "20") (name "/PUSH_FILT") (class "Default")
      (node (ref "U1") (pin "5") (pinfunction "GPIO3_5") (pintype "bidirectional"))
      (node (ref "U6") (pin "8") (pinfunction "O_8") (pintype "output"))
    )
    (net (code "21") (name "/ROTA") (class "Default")
      (node (ref "C23") (pin "2") (pinfunction "2_2") (pintype "passive"))
      (node (ref "R53") (pin "1") (pinfunction "1_1") (pintype "passive"))
      (node (ref "S1") (pin "A") (pinfunction "A_A") (pintype "bidirectional"))
      (node (ref "U3") (pin "5") (pinfunction "I_5") (pintype "input"))
    )
    (net (code "22") (name "/ROTA_FILT") (class "Default")
      (node (ref "U1") (pin "36") (pinfunction "GPIO24_36") (pintype "bidirectional"))
      (node (ref "U3") (pin "4") (pinfunction "O_4") (pintype "output"))
    )
    (net (code "23") (name "/ROTB") (class "Default")
      (node (ref "C22") (pin "2") (pinfunction "2_2") (pintype "passive"))
      (node (ref "R52") (pin "1") (pinfunction "1_1") (pintype "passive"))
      (node (ref "S1") (pin "B") (pinfunction "B_B") (pintype "bidirectional"))
      (node (ref "U3") (pin "11") (pinfunction "I_11") (pintype "input"))
    )
    (net (code "24") (name "/ROTB_FILT") (class "Default")
      (node (ref "U1") (pin "15") (pinfunction "GPIO12_15") (pintype "bidirectional"))
      (node (ref "U3") (pin "8") (pinfunction "O_8") (pintype "output"))
    )
    (net (code "25") (name "/ROTPUSH") (class "Default")
      (node (ref "C24") (pin "2") (pinfunction "2_2") (pintype "passive"))
      (node (ref "R54") (pin "1") (pinfunction "1_1") (pintype "passive"))
      (node (ref "S1") (pin "SW+") (pinfunction "SW+_SW+") (pintype "bidirectional"))
      (node (ref "U3") (pin "1") (pinfunction "I_1") (pintype "input"))
    )
    (net (code "26") (name "/RPUSH_FILT") (class "Default")
      (node (ref "U1") (pin "8") (pinfunction "GPIO6_8") (pintype "bidirectional"))
      (node (ref "U3") (pin "12") (pinfunction "O_12") (pintype "output"))
    )
    (net (code "27") (name "/RST") (class "Default")
      (node (ref "J6") (pin "5") (pinfunction "RST_5") (pintype "bidirectional"))
      (node (ref "R21") (pin "2") (pinfunction "2_2") (pintype "passive"))
    )
    (net (code "28") (name "/RUN") (class "Default")
      (node (ref "JP1") (pin "10") (pinfunction "10_10") (pintype "passive"))
      (node (ref "RUN") (pin "TP") (pinfunction "TP_TP") (pintype "input"))
      (node (ref "U1") (pin "26") (pinfunction "RUN_26") (pintype "bidirectional"))
    )
    (net (code "29") (name "/RX") (class "Default")
      (node (ref "RX") (pin "TP") (pinfunction "TP_TP") (pintype "input"))
      (node (ref "U1") (pin "3") (pinfunction "GPIO1_3") (pintype "bidirectional"))
    )
    (net (code "30") (name "/SCK") (class "Default")
      (node (ref "R14") (pin "1") (pinfunction "1_1") (pintype "passive"))
      (node (ref "U1") (pin "29") (pinfunction "GPIO18_29") (pintype "bidirectional"))
    )
    (net (code "31") (name "/SEL") (class "Default")
      (node (ref "U1") (pin "37") (pinfunction "GPIO25_37") (pintype "bidirectional"))
    )
    (net (code "32") (name "/SS") (class "Default")
      (node (ref "R29") (pin "1") (pinfunction "1_1") (pintype "passive"))
      (node (ref "U1") (pin "28") (pinfunction "GPIO17_28") (pintype "bidirectional"))
    )
    (net (code "33") (name "/SWCLK") (class "Default")
      (node (ref "JP1") (pin "4") (pinfunction "4_4") (pintype "passive"))
      (node (ref "SWCLK") (pin "TP") (pinfunction "TP_TP") (pintype "input"))
      (node (ref "U1") (pin "24") (pinfunction "SWCLK_24") (pintype "bidirectional"))
    )
    (net (code "34") (name "/SWDIO") (class "Default")
      (node (ref "JP1") (pin "2") (pinfunction "2_2") (pintype "passive"))
      (node (ref "SWDIO") (pin "TP") (pinfunction "TP_TP") (pintype "input"))
      (node (ref "U1") (pin "25") (pinfunction "SWDIO_25") (pintype "bidirectional"))
    )
    (net (code "35") (name "/SWO") (class "Default")
      (node (ref "JP1") (pin "6") (pinfunction "6_6") (pintype "passive"))
    )
    (net (code "36") (name "/TDI") (class "Default")
      (node (ref "JP1") (pin "8") (pinfunction "8_8") (pintype "passive"))
    )
    (net (code "37") (name "/TX") (class "Default")
      (node (ref "TX") (pin "TP") (pinfunction "TP_TP") (pintype "input"))
      (node (ref "U1") (pin "2") (pinfunction "GPIO0_2") (pintype "bidirectional"))
    )
    (net (code "38") (name "/USB_D+") (class "Default")
      (node (ref "D4") (pin "2") (pinfunction "CATHODE_2_2") (pintype "bidirectional"))
      (node (ref "J1") (pin "6") (pinfunction "D+_6") (pintype "passive"))
      (node (ref "J1") (pin "7") (pinfunction "D+_7") (pintype "passive"))
      (node (ref "USB-D+") (pin "TP") (pinfunction "TP_TP") (pintype "input"))
      (node (ref "USB_D+") (pin "2") (pinfunction "2_2") (pintype "passive"))
    )
    (net (code "39") (name "/USB_D-") (class "Default")
      (node (ref "D4") (pin "1") (pinfunction "CATHODE_1_1") (pintype "bidirectional"))
      (node (ref "J1") (pin "5") (pinfunction "D-_5") (pintype "passive"))
      (node (ref "J1") (pin "8") (pinfunction "D-_8") (pintype "passive"))
      (node (ref "USB-D-") (pin "TP") (pinfunction "TP_TP") (pintype "input"))
      (node (ref "USB_D-") (pin "2") (pinfunction "2_2") (pintype "passive"))
    )
    (net (code "40") (name "/USB_DM") (class "Default")
      (node (ref "R63") (pin "2") (pinfunction "2_2") (pintype "passive"))
      (node (ref "U1") (pin "46") (pinfunction "USB_DM_46") (pintype "bidirectional"))
    )
    (net (code "41") (name "/USB_DP") (class "Default")
      (node (ref "R38") (pin "2") (pinfunction "2_2") (pintype "passive"))
      (node (ref "U1") (pin "47") (pinfunction "USB_DP_47") (pintype "bidirectional"))
    )
    (net (code "42") (name "/VBUS_SENSE") (class "Default")
      (node (ref "C58") (pin "2") (pinfunction "2_2") (pintype "passive"))
      (node (ref "D7") (pin "3") (pinfunction "AC_3") (pintype "passive"))
      (node (ref "R50") (pin "1") (pinfunction "1_1") (pintype "passive"))
      (node (ref "R51") (pin "2") (pinfunction "2_2") (pintype "passive"))
      (node (ref "U1") (pin "38") (pinfunction "GPIO26_/_ADC0_38") (pintype "bidirectional"))
      (node (ref "VBUS_SENSE") (pin "TP") (pinfunction "TP_TP") (pintype "input"))
    )
    (net (code "43") (name "/VOSEN") (class "Default")
      (node (ref "C13") (pin "2") (pinfunction "2_2") (pintype "passive"))
      (node (ref "D2") (pin "3") (pinfunction "AC_3") (pintype "passive"))
      (node (ref "R36") (pin "1") (pinfunction "1_1") (pintype "passive"))
      (node (ref "R37") (pin "2") (pinfunction "2_2") (pintype "passive"))
      (node (ref "U1") (pin "40") (pinfunction "GPIO28_/_ADC2_40") (pintype "bidirectional"))
      (node (ref "VOSEN") (pin "TP") (pinfunction "TP_TP") (pintype "input"))
    )
    (net (code "44") (name "/VO_TPS") (class "Default")
      (node (ref "C19") (pin "2") (pinfunction "2_2") (pintype "passive"))
      (node (ref "C34") (pin "2") (pinfunction "2_2") (pintype "passive"))
      (node (ref "C39") (pin "1") (pinfunction "1_1") (pintype "passive"))
      (node (ref "C40") (pin "1") (pinfunction "1_1") (pintype "passive"))
      (node (ref "C41") (pin "1") (pinfunction "1_1") (pintype "passive"))
      (node (ref "C42") (pin "1") (pinfunction "1_1") (pintype "passive"))
      (node (ref "C43") (pin "1") (pinfunction "1_1") (pintype "passive"))
      (node (ref "L2") (pin "2") (pinfunction "2_2") (pintype "passive"))
      (node (ref "R11") (pin "2") (pinfunction "2_2") (pintype "passive"))
      (node (ref "R12") (pin "1") (pinfunction "1_1") (pintype "passive"))
      (node (ref "U4") (pin "5") (pinfunction "RS+_5") (pintype "power_in"))
    )
    (net (code "45") (name "1v1") (class "Default")
      (node (ref "C32") (pin "2") (pinfunction "2_2") (pintype "passive"))
      (node (ref "C33") (pin "2") (pinfunction "2_2") (pintype "passive"))
      (node (ref "C46") (pin "1") (pinfunction "1_1") (pintype "passive"))
      (node (ref "U1") (pin "23") (pinfunction "DVDD_1_23") (pintype "bidirectional"))
      (node (ref "U1") (pin "45") (pinfunction "VREG_VOUT_45") (pintype "bidirectional"))
      (node (ref "U1") (pin "50") (pinfunction "DVDD_2_50") (pintype "bidirectional"))
    )
    (net (code "46") (name "3V3MCU") (class "Default")
      (node (ref "3V3MCU") (pin "TP") (pinfunction "TP_TP") (pintype "input"))
      (node (ref "C12") (pin "2") (pinfunction "2_2") (pintype "passive"))
      (node (ref "C15") (pin "1") (pinfunction "1_1") (pintype "passive"))
      (node (ref "C16") (pin "2") (pinfunction "2_2") (pintype "passive"))
      (node (ref "C2") (pin "2") (pinfunction "2_2") (pintype "passive"))
      (node (ref "C20") (pin "2") (pinfunction "2_2") (pintype "passive"))
      (node (ref "C25") (pin "2") (pinfunction "2_2") (pintype "passive"))
      (node (ref "C26") (pin "1") (pinfunction "1_1") (pintype "passive"))
      (node (ref "C3") (pin "2") (pinfunction "2_2") (pintype "passive"))
      (node (ref "C31") (pin "2") (pinfunction "2_2") (pintype "passive"))
      (node (ref "C44") (pin "2") (pinfunction "2_2") (pintype "passive"))
      (node (ref "C45") (pin "1") (pinfunction "1_1") (pintype "passive"))
      (node (ref "C5") (pin "2") (pinfunction "2_2") (pintype "passive"))
      (node (ref "C50") (pin "2") (pinfunction "2_2") (pintype "passive"))
      (node (ref "C51") (pin "2") (pinfunction "2_2") (pintype "passive"))
      (node (ref "C52") (pin "2") (pinfunction "2_2") (pintype "passive"))
      (node (ref "C53") (pin "2") (pinfunction "2_2") (pintype "passive"))
      (node (ref "C57") (pin "1") (pinfunction "1_1") (pintype "passive"))
      (node (ref "C6") (pin "2") (pinfunction "2_2") (pintype "passive"))
      (node (ref "C60") (pin "2") (pinfunction "2_2") (pintype "passive"))
      (node (ref "C62") (pin "2") (pinfunction "2_2") (pintype "passive"))
      (node (ref "C7") (pin "2") (pinfunction "2_2") (pintype "passive"))
      (node (ref "C8") (pin "2") (pinfunction "2_2") (pintype "passive"))
      (node (ref "D2") (pin "2") (pinfunction "C_2") (pintype "passive"))
      (node (ref "D3") (pin "2") (pinfunction "C_2") (pintype "passive"))
      (node (ref "D7") (pin "2") (pinfunction "C_2") (pintype "passive"))
      (node (ref "DZ1") (pin "1") (pinfunction "K_1") (pintype "bidirectional"))
      (node (ref "J6") (pin "2") (pinfunction "VCC_2") (pintype "bidirectional"))
      (node (ref "JP1") (pin "1") (pinfunction "1_1") (pintype "passive"))
      (node (ref "L1") (pin "2") (pinfunction "2_2") (pintype "bidirectional"))
      (node (ref "LS1") (pin "1") (pinfunction "+_1") (pintype "bidirectional"))
      (node (ref "R13") (pin "2") (pinfunction "2_2") (pintype "passive"))
      (node (ref "R15") (pin "1") (pinfunction "1_1") (pintype "passive"))
      (node (ref "R19") (pin "2") (pinfunction "2_2") (pintype "passive"))
      (node (ref "R35") (pin "1") (pinfunction "1_1") (pintype "passive"))
      (node (ref "R40") (pin "2") (pinfunction "2_2") (pintype "passive"))
      (node (ref "R52") (pin "2") (pinfunction "2_2") (pintype "passive"))
      (node (ref "R53") (pin "2") (pinfunction "2_2") (pintype "passive"))
      (node (ref "R54") (pin "2") (pinfunction "2_2") (pintype "passive"))
      (node (ref "R57") (pin "2") (pinfunction "2_2") (pintype "passive"))
      (node (ref "R64") (pin "2") (pinfunction "2_2") (pintype "passive"))
      (node (ref "R66") (pin "1") (pinfunction "1_1") (pintype "passive"))
      (node (ref "R67") (pin "2") (pinfunction "2_2") (pintype "passive"))
      (node (ref "U1") (pin "1") (pinfunction "IOVDD_1_1") (pintype "bidirectional"))
      (node (ref "U1") (pin "10") (pinfunction "IOVDD_2_10") (pintype "bidirectional"))
      (node (ref "U1") (pin "22") (pinfunction "IOVDD_3_22") (pintype "bidirectional"))
      (node (ref "U1") (pin "33") (pinfunction "IOVDD_4_33") (pintype "bidirectional"))
      (node (ref "U1") (pin "42") (pinfunction "IOVDD_5_42") (pintype "bidirectional"))
      (node (ref "U1") (pin "44") (pinfunction "VREG_VIN_44") (pintype "bidirectional"))
      (node (ref "U1") (pin "48") (pinfunction "USB_VDD_48") (pintype "bidirectional"))
      (node (ref "U1") (pin "49") (pinfunction "IOVDD_6_49") (pintype "bidirectional"))
      (node (ref "U2") (pin "3") (pinfunction "VDD_3") (pintype "bidirectional"))
      (node (ref "U3") (pin "14") (pinfunction "VCC_14") (pintype "power_in"))
      (node (ref "U5") (pin "8") (pinfunction "VCC_8") (pintype "bidirectional"))
      (node (ref "U6") (pin "14") (pinfunction "VCC_14") (pintype "power_in"))
      (node (ref "U7") (pin "1") (pinfunction "VCC_1") (pintype "bidirectional"))
      (node (ref "U9") (pin "1") (pinfunction "VCC_1") (pintype "power_in"))
    )
    (net (code "47") (name "EN_DCDC") (class "Default")
      (node (ref "R27") (pin "2") (pinfunction "2_2") (pintype "passive"))
      (node (ref "R31") (pin "1") (pinfunction "1_1") (pintype "passive"))
      (node (ref "U1") (pin "4") (pinfunction "GPIO2_4") (pintype "bidirectional"))
    )
    (net (code "48") (name "GND") (class "Default")
      (node (ref "C10") (pin "1") (pinfunction "1_1") (pintype "passive"))
      (node (ref "C11") (pin "1") (pinfunction "1_1") (pintype "passive"))
      (node (ref "C12") (pin "1") (pinfunction "1_1") (pintype "passive"))
      (node (ref "C13") (pin "1") (pinfunction "1_1") (pintype "passive"))
      (node (ref "C14") (pin "1") (pinfunction "1_1") (pintype "passive"))
      (node (ref "C15") (pin "2") (pinfunction "2_2") (pintype "passive"))
      (node (ref "C16") (pin "1") (pinfunction "1_1") (pintype "passive"))
      (node (ref "C17") (pin "2") (pinfunction "2_2") (pintype "passive"))
      (node (ref "C18") (pin "2") (pinfunction "2_2") (pintype "passive"))
      (node (ref "C2") (pin "1") (pinfunction "1_1") (pintype "passive"))
      (node (ref "C20") (pin "1") (pinfunction "1_1") (pintype "passive"))
      (node (ref "C21") (pin "2") (pinfunction "2_2") (pintype "passive"))
      (node (ref "C22") (pin "1") (pinfunction "1_1") (pintype "passive"))
      (node (ref "C23") (pin "1") (pinfunction "1_1") (pintype "passive"))
      (node (ref "C24") (pin "1") (pinfunction "1_1") (pintype "passive"))
      (node (ref "C25") (pin "1") (pinfunction "1_1") (pintype "passive"))
      (node (ref "C26") (pin "2") (pinfunction "2_2") (pintype "passive"))
      (node (ref "C27") (pin "1") (pinfunction "1_1") (pintype "passive"))
      (node (ref "C28") (pin "1") (pinfunction "1_1") (pintype "passive"))
      (node (ref "C3") (pin "1") (pinfunction "1_1") (pintype "passive"))
      (node (ref "C30") (pin "1") (pinfunction "1_1") (pintype "passive"))
      (node (ref "C31") (pin "1") (pinfunction "1_1") (pintype "passive"))
      (node (ref "C32") (pin "1") (pinfunction "1_1") (pintype "passive"))
      (node (ref "C33") (pin "1") (pinfunction "1_1") (pintype "passive"))
      (node (ref "C34") (pin "1") (pinfunction "1_1") (pintype "passive"))
      (node (ref "C35") (pin "2") (pinfunction "2_2") (pintype "passive"))
      (node (ref "C36") (pin "1") (pinfunction "1_1") (pintype "passive"))
      (node (ref "C38") (pin "1") (pinfunction "1_1") (pintype "passive"))
      (node (ref "C39") (pin "2") (pinfunction "2_2") (pintype "passive"))
      (node (ref "C40") (pin "2") (pinfunction "2_2") (pintype "passive"))
      (node (ref "C41") (pin "2") (pinfunction "2_2") (pintype "passive"))
      (node (ref "C42") (pin "2") (pinfunction "2_2") (pintype "passive"))
      (node (ref "C44") (pin "1") (pinfunction "1_1") (pintype "passive"))
      (node (ref "C45") (pin "2") (pinfunction "2_2") (pintype "passive"))
      (node (ref "C46") (pin "2") (pinfunction "2_2") (pintype "passive"))
      (node (ref "C47") (pin "1") (pinfunction "1_1") (pintype "passive"))
      (node (ref "C48") (pin "1") (pinfunction "1_1") (pintype "passive"))
      (node (ref "C49") (pin "1") (pinfunction "1_1") (pintype "passive"))
      (node (ref "C5") (pin "1") (pinfunction "1_1") (pintype "passive"))
      (node (ref "C50") (pin "1") (pinfunction "1_1") (pintype "passive"))
      (node (ref "C51") (pin "1") (pinfunction "1_1") (pintype "passive"))
      (node (ref "C53") (pin "1") (pinfunction "1_1") (pintype "passive"))
      (node (ref "C54") (pin "1") (pinfunction "1_1") (pintype "passive"))
      (node (ref "C57") (pin "2") (pinfunction "2_2") (pintype "passive"))
      (node (ref "C58") (pin "1") (pinfunction "1_1") (pintype "passive"))
      (node (ref "C59") (pin "1") (pinfunction "1_1") (pintype "passive"))
      (node (ref "C6") (pin "1") (pinfunction "1_1") (pintype "passive"))
      (node (ref "C60") (pin "1") (pinfunction "1_1") (pintype "passive"))
      (node (ref "C61") (pin "1") (pinfunction "1_1") (pintype "passive"))
      (node (ref "C62") (pin "1") (pinfunction "1_1") (pintype "passive"))
      (node (ref "C63") (pin "1") (pinfunction "1_1") (pintype "passive"))
      (node (ref "C64") (pin "1") (pinfunction "1_1") (pintype "passive"))
      (node (ref "C65") (pin "1") (pinfunction "1_1") (pintype "passive"))
      (node (ref "C66") (pin "1") (pinfunction "1_1") (pintype "passive"))
      (node (ref "C7") (pin "1") (pinfunction "1_1") (pintype "passive"))
      (node (ref "C8") (pin "1") (pinfunction "1_1") (pintype "passive"))
      (node (ref "C9") (pin "2") (pinfunction "2_2") (pintype "passive"))
      (node (ref "D2") (pin "1") (pinfunction "A_1") (pintype "passive"))
      (node (ref "D6") (pin "1") (pinfunction "A_1") (pintype "bidirectional"))
      (node (ref "D7") (pin "1") (pinfunction "A_1") (pintype "passive"))
      (node (ref "D8") (pin "2") (pinfunction "A_2") (pintype "bidirectional"))
      (node (ref "DZ1") (pin "2") (pinfunction "A_2") (pintype "bidirectional"))
      (node (ref "GND") (pin "TP") (pinfunction "TP_TP") (pintype "input"))
      (node (ref "J6") (pin "1") (pinfunction "GND_1") (pintype "bidirectional"))
      (node (ref "JP1") (pin "3") (pinfunction "3_3") (pintype "passive"))
      (node (ref "JP1") (pin "5") (pinfunction "5_5") (pintype "passive"))
      (node (ref "JP1") (pin "7") (pinfunction "7_7") (pintype "passive"))
      (node (ref "JP1") (pin "9") (pinfunction "9_9") (pintype "passive"))
      (node (ref "OP1") (pin "3") (pinfunction "EMIT_3") (pintype "passive"))
      (node (ref "Q2") (pin "2") (pinfunction "S_2") (pintype "passive"))
      (node (ref "Q5") (pin "2") (pinfunction "S_2") (pintype "passive"))
      (node (ref "Q9") (pin "2") (pinfunction "S_2") (pintype "passive"))
      (node (ref "R16") (pin "2") (pinfunction "2_2") (pintype "passive"))
      (node (ref "R18") (pin "1") (pinfunction "1_1") (pintype "passive"))
      (node (ref "R22") (pin "2") (pinfunction "2_2") (pintype "passive"))
      (node (ref "R32") (pin "2") (pinfunction "2_2") (pintype "passive"))
      (node (ref "R36") (pin "2") (pinfunction "2_2") (pintype "passive"))
      (node (ref "R42") (pin "1") (pinfunction "1_1") (pintype "passive"))
      (node (ref "R43") (pin "1") (pinfunction "1_1") (pintype "passive"))
      (node (ref "R44") (pin "1") (pinfunction "1_1") (pintype "passive"))
      (node (ref "R45") (pin "1") (pinfunction "1_1") (pintype "passive"))
      (node (ref "R49") (pin "1") (pinfunction "1_1") (pintype "passive"))
      (node (ref "R50") (pin "2") (pinfunction "2_2") (pintype "passive"))
      (node (ref "R59") (pin "1") (pinfunction "1_1") (pintype "passive"))
      (node (ref "RSENSE") (pin "2") (pinfunction "2_2") (pintype "passive"))
      (node (ref "S1") (pin "C") (pinfunction "C_C") (pintype "bidirectional"))
      (node (ref "S1") (pin "SW-") (pinfunction "SW-_SW-") (pintype "bidirectional"))
      (node (ref "S2") (pin "2") (pinfunction "2_2") (pintype "passive"))
      (node (ref "U1") (pin "19") (pinfunction "TESTEN_19") (pintype "bidirectional"))
      (node (ref "U1") (pin "57") (pinfunction "GND_57") (pintype "bidirectional"))
      (node (ref "U11") (pin "4") (pinfunction "GND_4") (pintype "bidirectional"))
      (node (ref "U12") (pin "7") (pinfunction "GND_7") (pintype "bidirectional"))
      (node (ref "U12") (pin "9") (pinfunction "EP_9") (pintype "bidirectional"))
      (node (ref "U2") (pin "2") (pinfunction "VSS_2") (pintype "bidirectional"))
      (node (ref "U2") (pin "6") (pinfunction "AO_6") (pintype "bidirectional"))
      (node (ref "U3") (pin "7") (pinfunction "GND_7") (pintype "power_in"))
      (node (ref "U4") (pin "1") (pinfunction "GND_1") (pintype "passive"))
      (node (ref "U4") (pin "2") (pinfunction "GND_2_2") (pintype "passive"))
      (node (ref "U5") (pin "4") (pinfunction "GND_4") (pintype "bidirectional"))
      (node (ref "U6") (pin "7") (pinfunction "GND_7") (pintype "power_in"))
      (node (ref "U7") (pin "10") (pinfunction "A1_10") (pintype "bidirectional"))
      (node (ref "U7") (pin "16") (pinfunction "GND_16") (pintype "bidirectional"))
      (node (ref "U7") (pin "7") (pinfunction "A2_7") (pintype "bidirectional"))
      (node (ref "U7") (pin "8") (pinfunction "~{G}_8") (pintype "bidirectional"))
      (node (ref "U7") (pin "9") (pinfunction "A0_9") (pintype "bidirectional"))
      (node (ref "U8") (pin "2") (pinfunction "ANODE_1_2") (pintype "bidirectional"))
      (node (ref "X1") (pin "2") (pinfunction "GND_1_2") (pintype "bidirectional"))
      (node (ref "X1") (pin "4") (pinfunction "GND_2_4") (pintype "bidirectional"))
    )
    (net (code "49") (name "GND_IN") (class "Default")
      (node (ref "C55") (pin "2") (pinfunction "2_2") (pintype "passive"))
      (node (ref "C56") (pin "2") (pinfunction "2_2") (pintype "passive"))
      (node (ref "D1") (pin "A") (pinfunction "A_A") (pintype "passive"))
      (node (ref "D4") (pin "3") (pinfunction "COMMON_CATHODE_3") (pintype "bidirectional"))
      (node (ref "GND_IN") (pin "TP") (pinfunction "TP_TP") (pintype "input"))
      (node (ref "J1") (pin "1") (pinfunction "GND_1") (pintype "power_in"))
      (node (ref "J1") (pin "12") (pinfunction "GND_12") (pintype "power_in"))
      (node (ref "J1") (pin "S1") (pinfunction "SHIELD_S1") (pintype "passive"))
      (node (ref "J1") (pin "S2") (pinfunction "SHIELD_S2") (pintype "passive"))
      (node (ref "J1") (pin "S3") (pinfunction "SHIELD_S3") (pintype "passive"))
      (node (ref "J1") (pin "S4") (pinfunction "SHIELD_S4") (pintype "passive"))
      (node (ref "J1") (pin "S5") (pinfunction "SHIELD_S5") (pintype "passive"))
      (node (ref "J1") (pin "S6") (pinfunction "SHIELD_S6") (pintype "passive"))
      (node (ref "R34") (pin "1") (pinfunction "1_1") (pintype "passive"))
      (node (ref "R55") (pin "1") (pinfunction "1_1") (pintype "passive"))
      (node (ref "R56") (pin "1") (pinfunction "1_1") (pintype "passive"))
      (node (ref "RSENSE") (pin "1") (pinfunction "1_1") (pintype "passive"))
      (node (ref "U10") (pin "5") (pinfunction "GND_5") (pintype "bidirectional"))
      (node (ref "U9") (pin "2") (pinfunction "GND_2_2") (pintype "power_in"))
      (node (ref "U9") (pin "3") (pinfunction "GND_3") (pintype "power_in"))
    )
    (net (code "50") (name "IN+") (class "Default")
      (node (ref "C36") (pin "2") (pinfunction "2_2") (pintype "passive"))
      (node (ref "C56") (pin "1") (pinfunction "1_1") (pintype "passive"))
      (node (ref "D1") (pin "C") (pinfunction "K_C") (pintype "passive"))
      (node (ref "IN+") (pin "TP") (pinfunction "TP_TP") (pintype "input"))
      (node (ref "J1") (pin "11") (pinfunction "VBUS_11") (pintype "power_in"))
      (node (ref "J1") (pin "2") (pinfunction "VBUS_2") (pintype "power_in"))
      (node (ref "PTC1") (pin "2") (pinfunction "2_2") (pintype "passive"))
      (node (ref "R47") (pin "1") (pinfunction "1_1") (pintype "passive"))
      (node (ref "R51") (pin "1") (pinfunction "1_1") (pintype "passive"))
      (node (ref "R62") (pin "2") (pinfunction "2_2") (pintype "passive"))
    )
    (net (code "51") (name "IN_OVC") (class "Default")
      (node (ref "Q5") (pin "1") (pinfunction "G_1") (pintype "passive"))
      (node (ref "R48") (pin "2") (pinfunction "2_2") (pintype "passive"))
      (node (ref "R49") (pin "2") (pinfunction "2_2") (pintype "passive"))
      (node (ref "U6") (pin "13") (pinfunction "I_13") (pintype "input"))
    )
    (net (code "52") (name "ISENSE") (class "Default")
      (node (ref "ISENSE") (pin "TP") (pinfunction "TP_TP") (pintype "input"))
      (node (ref "U1") (pin "39") (pinfunction "GPIO27_/_ADC1_39") (pintype "bidirectional"))
      (node (ref "U4") (pin "3") (pinfunction "OUT_3") (pintype "output"))
    )
    (net (code "53") (name "Net-(BZ1-+)") (class "Default")
      (node (ref "BZ1") (pin "1") (pinfunction "+_1") (pintype "passive"))
      (node (ref "C27") (pin "2") (pinfunction "2_2") (pintype "passive"))
      (node (ref "L7") (pin "2") (pinfunction "2_2") (pintype "passive"))
      (node (ref "R61") (pin "2") (pinfunction "2_2") (pintype "passive"))
    )
    (net (code "54") (name "Net-(BZ1--)") (class "Default")
      (node (ref "BZ1") (pin "2") (pinfunction "-_2") (pintype "passive"))
      (node (ref "D3") (pin "3") (pinfunction "AC_3") (pintype "passive"))
      (node (ref "LS1") (pin "2") (pinfunction "-_2") (pintype "bidirectional"))
      (node (ref "Q9") (pin "3") (pinfunction "D_3") (pintype "passive"))
      (node (ref "R61") (pin "1") (pinfunction "1_1") (pintype "passive"))
    )
    (net (code "55") (name "Net-(C10-Pad2)") (class "Default")
      (node (ref "C10") (pin "2") (pinfunction "2_2") (pintype "passive"))
      (node (ref "R13") (pin "1") (pinfunction "1_1") (pintype "passive"))
      (node (ref "R65") (pin "2") (pinfunction "2_2") (pintype "passive"))
      (node (ref "S2") (pin "4") (pinfunction "4_4") (pintype "passive"))
    )
    (net (code "56") (name "Net-(C37-Pad1)") (class "Default")
      (node (ref "C37") (pin "1") (pinfunction "1_1") (pintype "passive"))
      (node (ref "R44") (pin "2") (pinfunction "2_2") (pintype "passive"))
    )
    (net (code "57") (name "Net-(C52-Pad1)") (class "Default")
      (node (ref "C52") (pin "1") (pinfunction "1_1") (pintype "passive"))
      (node (ref "FB_ADJ") (pin "1") (pinfunction "1_1") (pintype "passive"))
      (node (ref "R15") (pin "2") (pinfunction "2_2") (pintype "passive"))
      (node (ref "R16") (pin "1") (pinfunction "1_1") (pintype "passive"))
    )
    (net (code "58") (name "Net-(D5-A)") (class "Default")
      (node (ref "D5") (pin "2") (pinfunction "A_2") (pintype "bidirectional"))
      (node (ref "OP1") (pin "1") (pinfunction "A_1") (pintype "passive"))
    )
    (net (code "59") (name "Net-(J6-DC)") (class "Default")
      (node (ref "J6") (pin "6") (pinfunction "DC_6") (pintype "bidirectional"))
      (node (ref "R24") (pin "2") (pinfunction "2_2") (pintype "passive"))
    )
    (net (code "60") (name "Net-(L3-Pad2)") (class "Default")
      (node (ref "L3") (pin "2") (pinfunction "2_2") (pintype "passive"))
      (node (ref "R26") (pin "1") (pinfunction "1_1") (pintype "passive"))
    )
    (net (code "61") (name "Net-(L4-Pad2)") (class "Default")
      (node (ref "L4") (pin "2") (pinfunction "2_2") (pintype "passive"))
      (node (ref "R22") (pin "1") (pinfunction "1_1") (pintype "passive"))
    )
    (net (code "62") (name "Net-(LED1-C)") (class "Default")
      (node (ref "LED1") (pin "K") (pinfunction "C_K") (pintype "passive"))
      (node (ref "Q2") (pin "3") (pinfunction "D_3") (pintype "passive"))
    )
    (net (code "63") (name "Net-(LED1-PadA)") (class "Default")
      (node (ref "LED1") (pin "A") (pinfunction "A_A") (pintype "passive"))
      (node (ref "R35") (pin "2") (pinfunction "2_2") (pintype "passive"))
    )
    (net (code "64") (name "Net-(Q2-G)") (class "Default")
      (node (ref "Q2") (pin "1") (pinfunction "G_1") (pintype "passive"))
      (node (ref "R31") (pin "2") (pinfunction "2_2") (pintype "passive"))
    )
    (net (code "65") (name "Net-(Q4-D)") (class "Default")
      (node (ref "Q4") (pin "3") (pinfunction "D_3") (pintype "passive"))
      (node (ref "R41") (pin "1") (pinfunction "1_1") (pintype "passive"))
    )
    (net (code "66") (name "Net-(Q9-G)") (class "Default")
      (node (ref "Q9") (pin "1") (pinfunction "G_1") (pintype "passive"))
      (node (ref "R28") (pin "2") (pinfunction "2_2") (pintype "passive"))
      (node (ref "R32") (pin "1") (pinfunction "1_1") (pintype "passive"))
    )
    (net (code "67") (name "Net-(R38-Pad1)") (class "Default")
      (node (ref "R38") (pin "1") (pinfunction "1_1") (pintype "passive"))
      (node (ref "USB_D+") (pin "1") (pinfunction "1_1") (pintype "passive"))
    )
    (net (code "68") (name "Net-(R63-Pad1)") (class "Default")
      (node (ref "R63") (pin "1") (pinfunction "1_1") (pintype "passive"))
      (node (ref "USB_D-") (pin "1") (pinfunction "1_1") (pintype "passive"))
    )
    (net (code "69") (name "Net-(U2-SCL)") (class "Default")
      (node (ref "R58") (pin "2") (pinfunction "2_2") (pintype "passive"))
      (node (ref "U2") (pin "5") (pinfunction "SCL_5") (pintype "bidirectional"))
    )
    (net (code "70") (name "Net-(U2-SDA)") (class "Default")
      (node (ref "R60") (pin "2") (pinfunction "2_2") (pintype "passive"))
      (node (ref "U2") (pin "4") (pinfunction "SDA_4") (pintype "bidirectional"))
    )
    (net (code "71") (name "Net-(U3A-I)") (class "Default")
      (node (ref "C49") (pin "2") (pinfunction "2_2") (pintype "passive"))
      (node (ref "R25") (pin "2") (pinfunction "2_2") (pintype "passive"))
      (node (ref "U3") (pin "13") (pinfunction "I_13") (pintype "input"))
    )
    (net (code "72") (name "Net-(U3B-O)") (class "Default")
      (node (ref "R2") (pin "1") (pinfunction "1_1") (pintype "passive"))
      (node (ref "U3") (pin "10") (pinfunction "O_10") (pintype "output"))
    )
    (net (code "73") (name "Net-(U3C-I)") (class "Default")
      (node (ref "C47") (pin "2") (pinfunction "2_2") (pintype "passive"))
      (node (ref "R2") (pin "2") (pinfunction "2_2") (pintype "passive"))
      (node (ref "U3") (pin "9") (pinfunction "I_9") (pintype "input"))
    )
    (net (code "74") (name "Net-(U3D-O)") (class "Default")
      (node (ref "R25") (pin "1") (pinfunction "1_1") (pintype "passive"))
      (node (ref "U3") (pin "2") (pinfunction "O_2") (pintype "output"))
    )
    (net (code "75") (name "Net-(U3E-I)") (class "Default")
      (node (ref "C48") (pin "2") (pinfunction "2_2") (pintype "passive"))
      (node (ref "R20") (pin "2") (pinfunction "2_2") (pintype "passive"))
      (node (ref "U3") (pin "3") (pinfunction "I_3") (pintype "input"))
    )
    (net (code "76") (name "Net-(U3F-O)") (class "Default")
      (node (ref "R20") (pin "1") (pinfunction "1_1") (pintype "passive"))
      (node (ref "U3") (pin "6") (pinfunction "O_6") (pintype "output"))
    )
    (net (code "77") (name "Net-(U4-RS-)") (class "Default")
      (node (ref "C43") (pin "2") (pinfunction "2_2") (pintype "passive"))
      (node (ref "R1") (pin "1") (pinfunction "1_1") (pintype "passive"))
      (node (ref "U4") (pin "4") (pinfunction "RS-_4") (pintype "input"))
    )
    (net (code "78") (name "Net-(U6A-O)") (class "Default")
      (node (ref "R39") (pin "1") (pinfunction "1_1") (pintype "passive"))
      (node (ref "U6") (pin "12") (pinfunction "O_12") (pintype "output"))
    )
    (net (code "79") (name "Net-(U6B-I)") (class "Default")
      (node (ref "C54") (pin "2") (pinfunction "2_2") (pintype "passive"))
      (node (ref "R39") (pin "2") (pinfunction "2_2") (pintype "passive"))
      (node (ref "U6") (pin "11") (pinfunction "I_11") (pintype "input"))
    )
    (net (code "80") (name "Net-(U6C-I)") (class "Default")
      (node (ref "C14") (pin "2") (pinfunction "2_2") (pintype "passive"))
      (node (ref "R33") (pin "2") (pinfunction "2_2") (pintype "passive"))
      (node (ref "U6") (pin "9") (pinfunction "I_9") (pintype "input"))
    )
    (net (code "81") (name "Net-(U6D-O)") (class "Default")
      (node (ref "R23") (pin "1") (pinfunction "1_1") (pintype "passive"))
      (node (ref "U6") (pin "2") (pinfunction "O_2") (pintype "output"))
    )
    (net (code "82") (name "Net-(U6E-I)") (class "Default")
      (node (ref "C11") (pin "2") (pinfunction "2_2") (pintype "passive"))
      (node (ref "R23") (pin "2") (pinfunction "2_2") (pintype "passive"))
      (node (ref "U6") (pin "3") (pinfunction "I_3") (pintype "input"))
    )
    (net (code "83") (name "Net-(U6F-O)") (class "Default")
      (node (ref "R33") (pin "1") (pinfunction "1_1") (pintype "passive"))
      (node (ref "U6") (pin "6") (pinfunction "O_6") (pintype "output"))
    )
    (net (code "84") (name "Net-(U7-DRAIN0)") (class "Default")
      (node (ref "R6") (pin "1") (pinfunction "1_1") (pintype "passive"))
      (node (ref "U7") (pin "3") (pinfunction "DRAIN0_3") (pintype "bidirectional"))
    )
    (net (code "85") (name "Net-(U7-DRAIN1)") (class "Default")
      (node (ref "R5") (pin "1") (pinfunction "1_1") (pintype "passive"))
      (node (ref "U7") (pin "4") (pinfunction "DRAIN1_4") (pintype "bidirectional"))
    )
    (net (code "86") (name "Net-(U7-DRAIN2)") (class "Default")
      (node (ref "R4") (pin "1") (pinfunction "1_1") (pintype "passive"))
      (node (ref "U7") (pin "5") (pinfunction "DRAIN2_5") (pintype "bidirectional"))
    )
    (net (code "87") (name "Net-(U7-DRAIN3)") (class "Default")
      (node (ref "R3") (pin "1") (pinfunction "1_1") (pintype "passive"))
      (node (ref "U7") (pin "6") (pinfunction "DRAIN3_6") (pintype "bidirectional"))
    )
    (net (code "88") (name "Net-(U7-DRAIN4)") (class "Default")
      (node (ref "R10") (pin "1") (pinfunction "1_1") (pintype "passive"))
      (node (ref "U7") (pin "11") (pinfunction "DRAIN4_11") (pintype "bidirectional"))
    )
    (net (code "89") (name "Net-(U7-DRAIN5)") (class "Default")
      (node (ref "R9") (pin "1") (pinfunction "1_1") (pintype "passive"))
      (node (ref "U7") (pin "12") (pinfunction "DRAIN5_12") (pintype "bidirectional"))
    )
    (net (code "90") (name "Net-(U7-DRAIN6)") (class "Default")
      (node (ref "R8") (pin "1") (pinfunction "1_1") (pintype "passive"))
      (node (ref "U7") (pin "13") (pinfunction "DRAIN6_13") (pintype "bidirectional"))
    )
    (net (code "91") (name "Net-(U7-DRAIN7)") (class "Default")
      (node (ref "R7") (pin "1") (pinfunction "1_1") (pintype "passive"))
      (node (ref "U7") (pin "14") (pinfunction "DRAIN7_14") (pintype "bidirectional"))
    )
    (net (code "92") (name "Net-(U7-SCL)") (class "Default")
      (node (ref "L5") (pin "1") (pinfunction "1_1") (pintype "passive"))
      (node (ref "U7") (pin "15") (pinfunction "SCL_15") (pintype "bidirectional"))
    )
    (net (code "93") (name "Net-(U7-SDA)") (class "Default")
      (node (ref "L6") (pin "1") (pinfunction "1_1") (pintype "passive"))
      (node (ref "U7") (pin "2") (pinfunction "SDA_2") (pintype "bidirectional"))
    )
    (net (code "94") (name "Net-(U9-IN)") (class "Default")
      (node (ref "C55") (pin "1") (pinfunction "1_1") (pintype "passive"))
      (node (ref "R34") (pin "2") (pinfunction "2_2") (pintype "passive"))
      (node (ref "R59") (pin "2") (pinfunction "2_2") (pintype "passive"))
      (node (ref "U9") (pin "4") (pinfunction "IN_4") (pintype "input"))
    )
    (net (code "95") (name "Net-(U9-OUT)") (class "Default")
      (node (ref "R48") (pin "1") (pinfunction "1_1") (pintype "passive"))
      (node (ref "U9") (pin "5") (pinfunction "OUT_5") (pintype "output"))
    )
    (net (code "96") (name "Net-(U10-SEL)") (class "Default")
      (node (ref "R62") (pin "1") (pinfunction "1_1") (pintype "passive"))
      (node (ref "U10") (pin "11") (pinfunction "SEL_11") (pintype "bidirectional"))
    )
    (net (code "97") (name "Net-(U10-VIN)") (class "Default")
      (node (ref "R47") (pin "2") (pinfunction "2_2") (pintype "passive"))
      (node (ref "U10") (pin "2") (pinfunction "VIN_2") (pintype "bidirectional"))
    )
    (net (code "98") (name "Net-(U11-BST)") (class "Default")
      (node (ref "C4") (pin "2") (pinfunction "2_2") (pintype "passive"))
      (node (ref "U11") (pin "6") (pinfunction "BST_6") (pintype "bidirectional"))
    )
    (net (code "99") (name "Net-(U11-SW)") (class "Default")
      (node (ref "C4") (pin "1") (pinfunction "1_1") (pintype "passive"))
      (node (ref "L1") (pin "1") (pinfunction "1_1") (pintype "bidirectional"))
      (node (ref "U11") (pin "5") (pinfunction "SW_5") (pintype "bidirectional"))
    )
    (net (code "100") (name "Net-(U12-BST)") (class "Default")
      (node (ref "C29") (pin "1") (pinfunction "1_1") (pintype "passive"))
      (node (ref "U12") (pin "1") (pinfunction "BST_1") (pintype "bidirectional"))
    )
    (net (code "101") (name "Net-(U12-COMP)") (class "Default")
      (node (ref "C37") (pin "2") (pinfunction "2_2") (pintype "passive"))
      (node (ref "C38") (pin "2") (pinfunction "2_2") (pintype "passive"))
      (node (ref "U12") (pin "6") (pinfunction "COMP_6") (pintype "bidirectional"))
    )
    (net (code "102") (name "Net-(U12-FB)") (class "Default")
      (node (ref "C19") (pin "1") (pinfunction "1_1") (pintype "passive"))
      (node (ref "C65") (pin "2") (pinfunction "2_2") (pintype "passive"))
      (node (ref "R10") (pin "2") (pinfunction "2_2") (pintype "passive"))
      (node (ref "R11") (pin "1") (pinfunction "1_1") (pintype "passive"))
      (node (ref "R3") (pin "2") (pinfunction "2_2") (pintype "passive"))
      (node (ref "R30") (pin "2") (pinfunction "2_2") (pintype "passive"))
      (node (ref "R4") (pin "2") (pinfunction "2_2") (pintype "passive"))
      (node (ref "R45") (pin "2") (pinfunction "2_2") (pintype "passive"))
      (node (ref "R5") (pin "2") (pinfunction "2_2") (pintype "passive"))
      (node (ref "R6") (pin "2") (pinfunction "2_2") (pintype "passive"))
      (node (ref "R7") (pin "2") (pinfunction "2_2") (pintype "passive"))
      (node (ref "R8") (pin "2") (pinfunction "2_2") (pintype "passive"))
      (node (ref "R9") (pin "2") (pinfunction "2_2") (pintype "passive"))
      (node (ref "U12") (pin "5") (pinfunction "FB_5") (pintype "bidirectional"))
    )
    (net (code "103") (name "Net-(U12-SS)") (class "Default")
      (node (ref "C30") (pin "2") (pinfunction "2_2") (pintype "passive"))
      (node (ref "U12") (pin "4") (pinfunction "SS_4") (pintype "bidirectional"))
    )
    (net (code "104") (name "Net-(X1-CRYSTAL_2)") (class "Default")
      (node (ref "C61") (pin "2") (pinfunction "2_2") (pintype "passive"))
      (node (ref "R46") (pin "2") (pinfunction "2_2") (pintype "passive"))
      (node (ref "X1") (pin "3") (pinfunction "CRYSTAL_2_3") (pintype "bidirectional"))
    )
    (net (code "105") (name "PEDAL+") (class "Default")
      (node (ref "L3") (pin "1") (pinfunction "1_1") (pintype "passive"))
      (node (ref "PEDAL+") (pin "TP") (pinfunction "TP_TP") (pintype "input"))
    )
    (net (code "106") (name "PEDAL-") (class "Default")
      (node (ref "L4") (pin "1") (pinfunction "1_1") (pintype "passive"))
      (node (ref "PEDAL-") (pin "TP") (pinfunction "TP_TP") (pintype "input"))
    )
    (net (code "107") (name "PEDAL_IP") (class "Default")
      (node (ref "U1") (pin "11") (pinfunction "GPIO8_11") (pintype "bidirectional"))
      (node (ref "U6") (pin "4") (pinfunction "O_4") (pintype "output"))
    )
    (net (code "108") (name "QSPI_SCLK") (class "Default")
      (node (ref "U1") (pin "52") (pinfunction "QSPI_SCLK_52") (pintype "bidirectional"))
      (node (ref "U5") (pin "6") (pinfunction "CLK_6") (pintype "bidirectional"))
    )
    (net (code "109") (name "QSPI_SD0") (class "Default")
      (node (ref "U1") (pin "53") (pinfunction "QSPI_SD0_53") (pintype "bidirectional"))
      (node (ref "U5") (pin "5") (pinfunction "DI(IO0)_5") (pintype "bidirectional"))
    )
    (net (code "110") (name "QSPI_SD1") (class "Default")
      (node (ref "U1") (pin "55") (pinfunction "QSPI_SD1_55") (pintype "bidirectional"))
      (node (ref "U5") (pin "2") (pinfunction "DO(IO1)_2") (pintype "bidirectional"))
    )
    (net (code "111") (name "QSPI_SD2") (class "Default")
      (node (ref "U1") (pin "54") (pinfunction "QSPI_SD2_54") (pintype "bidirectional"))
      (node (ref "U5") (pin "3") (pinfunction "/WP_(IO2)_3") (pintype "bidirectional"))
    )
    (net (code "112") (name "QSPI_SD3") (class "Default")
      (node (ref "U1") (pin "51") (pinfunction "QSPI_SD3_51") (pintype "bidirectional"))
      (node (ref "U5") (pin "7") (pinfunction "/HOLD_OR_/RESET_(IO3)_7") (pintype "bidirectional"))
    )
    (net (code "113") (name "QSPI_SS") (class "Default")
      (node (ref "R40") (pin "1") (pinfunction "1_1") (pintype "passive"))
      (node (ref "U1") (pin "56") (pinfunction "QSPI_SS_N_56") (pintype "bidirectional"))
      (node (ref "U5") (pin "1") (pinfunction "/CS_1") (pintype "bidirectional"))
    )
    (net (code "114") (name "SAFETY_EN_DCDC") (class "Default")
      (node (ref "Q4") (pin "1") (pinfunction "G_1") (pintype "passive"))
      (node (ref "Q5") (pin "3") (pinfunction "D_3") (pintype "passive"))
      (node (ref "R27") (pin "1") (pinfunction "1_1") (pintype "passive"))
      (node (ref "R42") (pin "2") (pinfunction "2_2") (pintype "passive"))
    )
    (net (code "115") (name "SCL") (class "Default")
      (node (ref "L5") (pin "2") (pinfunction "2_2") (pintype "passive"))
      (node (ref "R58") (pin "1") (pinfunction "1_1") (pintype "passive"))
      (node (ref "R67") (pin "1") (pinfunction "1_1") (pintype "passive"))
      (node (ref "SCL") (pin "TP") (pinfunction "TP_TP") (pintype "input"))
      (node (ref "U1") (pin "7") (pinfunction "GPIO5_7") (pintype "bidirectional"))
    )
    (net (code "116") (name "SDA") (class "Default")
      (node (ref "L6") (pin "2") (pinfunction "2_2") (pintype "passive"))
      (node (ref "R60") (pin "1") (pinfunction "1_1") (pintype "passive"))
      (node (ref "R64") (pin "1") (pinfunction "1_1") (pintype "passive"))
      (node (ref "SDA") (pin "TP") (pinfunction "TP_TP") (pintype "input"))
      (node (ref "U1") (pin "6") (pinfunction "GPIO4_6") (pintype "bidirectional"))
    )
    (net (code "117") (name "VCC") (class "Default")
      (node (ref "C17") (pin "1") (pinfunction "1_1") (pintype "passive"))
      (node (ref "C18") (pin "1") (pinfunction "1_1") (pintype "passive"))
      (node (ref "C21") (pin "1") (pinfunction "1_1") (pintype "passive"))
      (node (ref "C28") (pin "2") (pinfunction "2_2") (pintype "passive"))
      (node (ref "C35") (pin "1") (pinfunction "1_1") (pintype "passive"))
      (node (ref "C63") (pin "2") (pinfunction "2_2") (pintype "passive"))
      (node (ref "C64") (pin "2") (pinfunction "2_2") (pintype "passive"))
      (node (ref "D5") (pin "1") (pinfunction "K_1") (pintype "bidirectional"))
      (node (ref "L7") (pin "1") (pinfunction "1_1") (pintype "passive"))
      (node (ref "PTC1") (pin "1") (pinfunction "1_1") (pintype "passive"))
      (node (ref "R41") (pin "2") (pinfunction "2_2") (pintype "passive"))
      (node (ref "U11") (pin "2") (pinfunction "EN_2") (pintype "bidirectional"))
      (node (ref "U11") (pin "3") (pinfunction "VIN_3") (pintype "bidirectional"))
      (node (ref "U12") (pin "2") (pinfunction "VIN_2") (pintype "bidirectional"))
    )
    (net (code "118") (name "VOUT") (class "Default")
      (node (ref "D8") (pin "1") (pinfunction "K_1") (pintype "bidirectional"))
      (node (ref "R1") (pin "2") (pinfunction "2_2") (pintype "passive"))
      (node (ref "R12") (pin "2") (pinfunction "2_2") (pintype "passive"))
      (node (ref "R37") (pin "1") (pinfunction "1_1") (pintype "passive"))
      (node (ref "VOUT") (pin "TP") (pinfunction "TP_TP") (pintype "input"))
    )
    (net (code "119") (name "XIN") (class "Default")
      (node (ref "C59") (pin "2") (pinfunction "2_2") (pintype "passive"))
      (node (ref "U1") (pin "20") (pinfunction "XIN_20") (pintype "bidirectional"))
      (node (ref "X1") (pin "1") (pinfunction "CRYSTAL_1_1") (pintype "bidirectional"))
    )
    (net (code "120") (name "XOUT") (class "Default")
      (node (ref "R46") (pin "1") (pinfunction "1_1") (pintype "passive"))
      (node (ref "U1") (pin "21") (pinfunction "XOUT_21") (pintype "bidirectional"))
    )
    (net (code "121") (name "unconnected-(D3-A-Pad1)") (class "Default")
      (node (ref "D3") (pin "1") (pinfunction "A_1") (pintype "passive"))
    )
    (net (code "122") (name "unconnected-(J1-SBU1-Pad10)") (class "Default")
      (node (ref "J1") (pin "10") (pinfunction "SBU1_10") (pintype "passive"))
    )
    (net (code "123") (name "unconnected-(J1-SBU2-Pad4)") (class "Default")
      (node (ref "J1") (pin "4") (pinfunction "SBU2_4") (pintype "passive"))
    )
    (net (code "124") (name "unconnected-(LS1-DUMMY-Pad3)") (class "Default")
      (node (ref "LS1") (pin "3") (pinfunction "DUMMY_3") (pintype "bidirectional"))
    )
    (net (code "125") (name "unconnected-(S2-Pad1)") (class "Default")
      (node (ref "S2") (pin "1") (pinfunction "1_1") (pintype "passive"))
    )
    (net (code "126") (name "unconnected-(S2-Pad3)") (class "Default")
      (node (ref "S2") (pin "3") (pinfunction "3_3") (pintype "passive"))
    )
    (net (code "127") (name "unconnected-(U1-GPIO10-Pad13)") (class "Default")
      (node (ref "U1") (pin "13") (pinfunction "GPIO10_13") (pintype "bidirectional"))
    )
    (net (code "128") (name "unconnected-(U1-GPIO11-Pad14)") (class "Default")
      (node (ref "U1") (pin "14") (pinfunction "GPIO11_14") (pintype "bidirectional"))
    )
    (net (code "129") (name "unconnected-(U1-GPIO13-Pad16)") (class "Default")
      (node (ref "U1") (pin "16") (pinfunction "GPIO13_16") (pintype "bidirectional"))
    )
    (net (code "130") (name "unconnected-(U1-GPIO14-Pad17)") (class "Default")
      (node (ref "U1") (pin "17") (pinfunction "GPIO14_17") (pintype "bidirectional"))
    )
    (net (code "131") (name "unconnected-(U1-GPIO15-Pad18)") (class "Default")
      (node (ref "U1") (pin "18") (pinfunction "GPIO15_18") (pintype "bidirectional"))
    )
    (net (code "132") (name "unconnected-(U1-GPIO20-Pad31)") (class "Default")
      (node (ref "U1") (pin "31") (pinfunction "GPIO20_31") (pintype "bidirectional"))
    )
    (net (code "133") (name "unconnected-(U1-GPIO22-Pad34)") (class "Default")
      (node (ref "U1") (pin "34") (pinfunction "GPIO22_34") (pintype "bidirectional"))
    )
    (net (code "134") (name "unconnected-(U1-GPIO23-Pad35)") (class "Default")
      (node (ref "U1") (pin "35") (pinfunction "GPIO23_35") (pintype "bidirectional"))
    )
    (net (code "135") (name "unconnected-(U1-GPIO29_{slash}_ADC3-Pad41)") (class "Default")
      (node (ref "U1") (pin "41") (pinfunction "GPIO29_/_ADC3_41") (pintype "bidirectional"))
    )
    (net (code "136") (name "unconnected-(U8-ANODE_2-Pad3)") (class "Default")
      (node (ref "U8") (pin "3") (pinfunction "ANODE_2_3") (pintype "bidirectional"))
    )
    (net (code "137") (name "unconnected-(U10-NC_1-Pad3)") (class "Default")
      (node (ref "U10") (pin "3") (pinfunction "NC_1_3") (pintype "bidirectional"))
    )
    (net (code "138") (name "unconnected-(U10-NC_2-Pad4)") (class "Default")
      (node (ref "U10") (pin "4") (pinfunction "NC_2_4") (pintype "bidirectional"))
    )
    (net (code "139") (name "unconnected-(U10-NC_3-Pad9)") (class "Default")
      (node (ref "U10") (pin "9") (pinfunction "NC_3_9") (pintype "bidirectional"))
    )
    (net (code "140") (name "unconnected-(U10-NC_4-Pad10)") (class "Default")
      (node (ref "U10") (pin "10") (pinfunction "NC_4_10") (pintype "bidirectional"))
    )
    (net (code "141") (name "unconnected-(U10-NC_5-Pad14)") (class "Default")
      (node (ref "U10") (pin "14") (pinfunction "NC_5_14") (pintype "bidirectional"))
    )
    (net (code "142") (name "unconnected-(U10-NC_6-Pad15)") (class "Default")
      (node (ref "U10") (pin "15") (pinfunction "NC_6_15") (pintype "bidirectional"))
    )
    (net (code "143") (name "unconnected-(U10-TST1-Pad6)") (class "Default")
      (node (ref "U10") (pin "6") (pinfunction "TST1_6") (pintype "bidirectional"))
    )
    (net (code "144") (name "unconnected-(U10-TST2-Pad7)") (class "Default")
      (node (ref "U10") (pin "7") (pinfunction "TST2_7") (pintype "bidirectional"))
    )
    (net (code "145") (name "unconnected-(U10-TST3-Pad8)") (class "Default")
      (node (ref "U10") (pin "8") (pinfunction "TST3_8") (pintype "bidirectional"))
    )
    (net (code "146") (name "unconnected-(U10-VBUS-Pad16)") (class "Default")
      (node (ref "U10") (pin "16") (pinfunction "VBUS_16") (pintype "bidirectional"))
    )
    (net (code "147") (name "unconnected-(U10-VBUSG-Pad1)") (class "Default")
      (node (ref "U10") (pin "1") (pinfunction "VBUSG_1") (pintype "bidirectional"))
    )
  )
)
